# cape.net
KiCad netlist of a schematic drawn in EAGLE
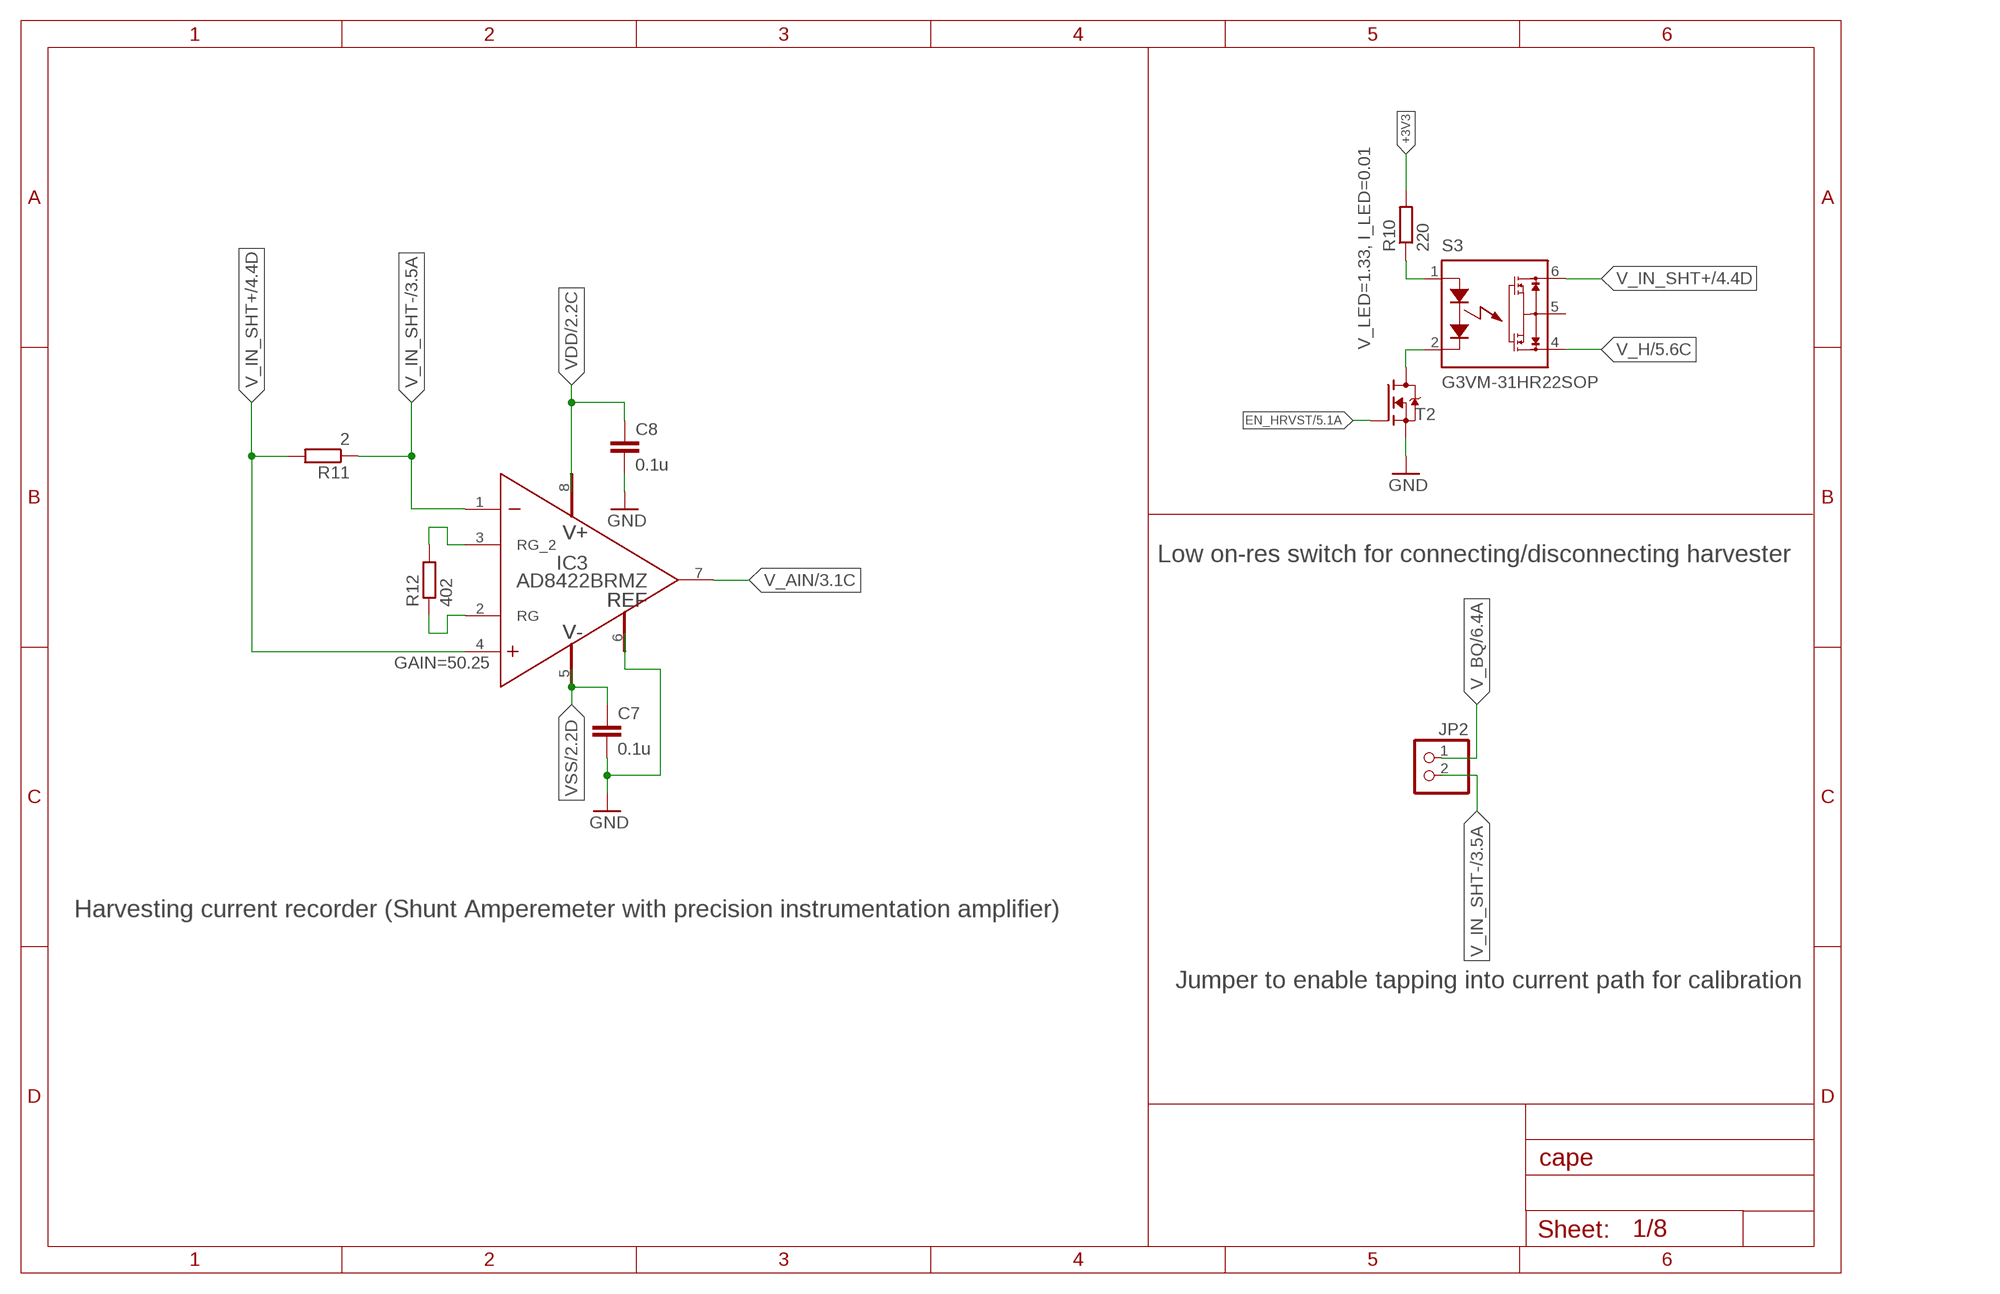
[diagram p0: schematic, sheet 1]
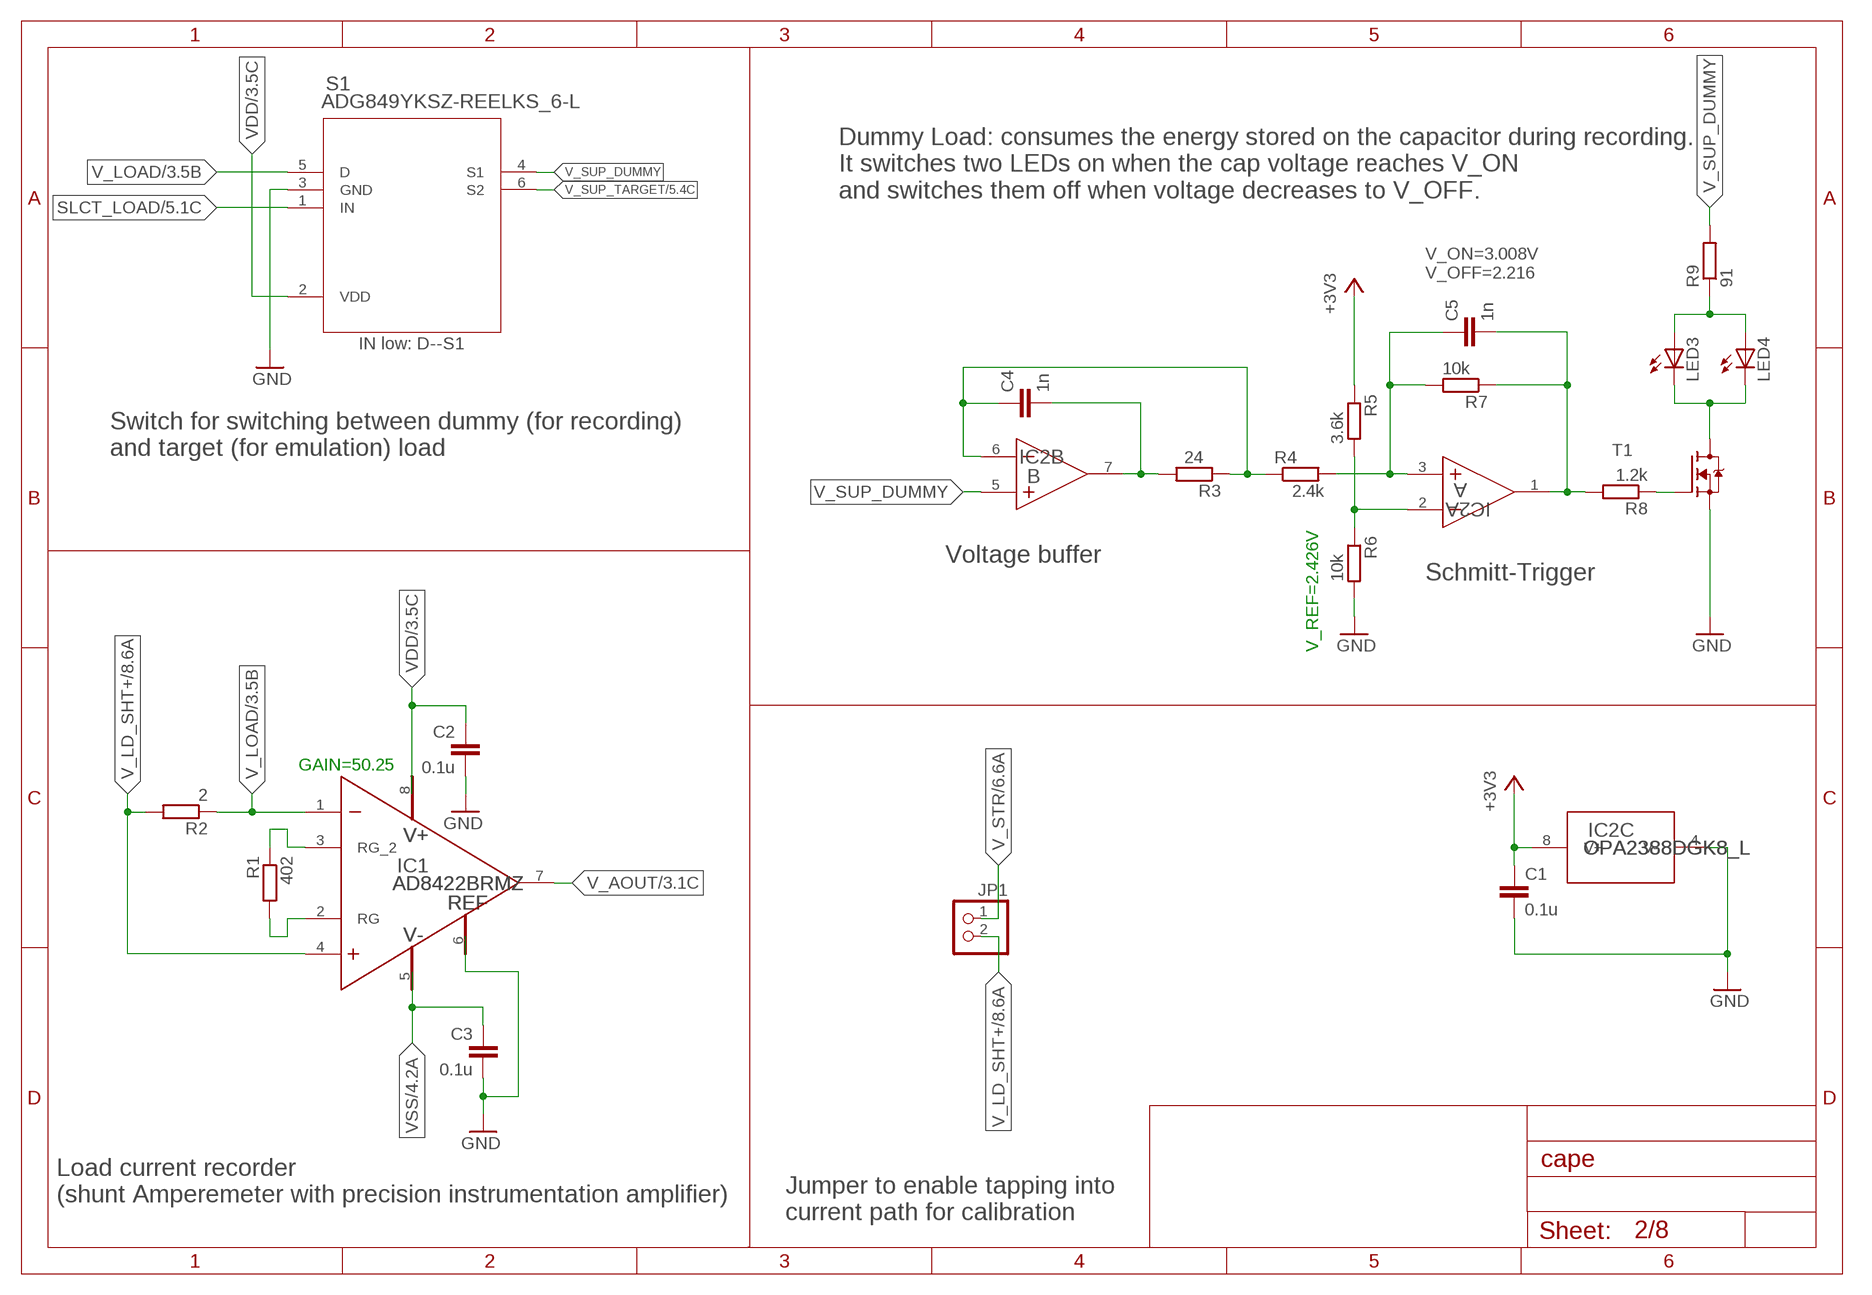
[diagram p1: schematic, sheet 2]
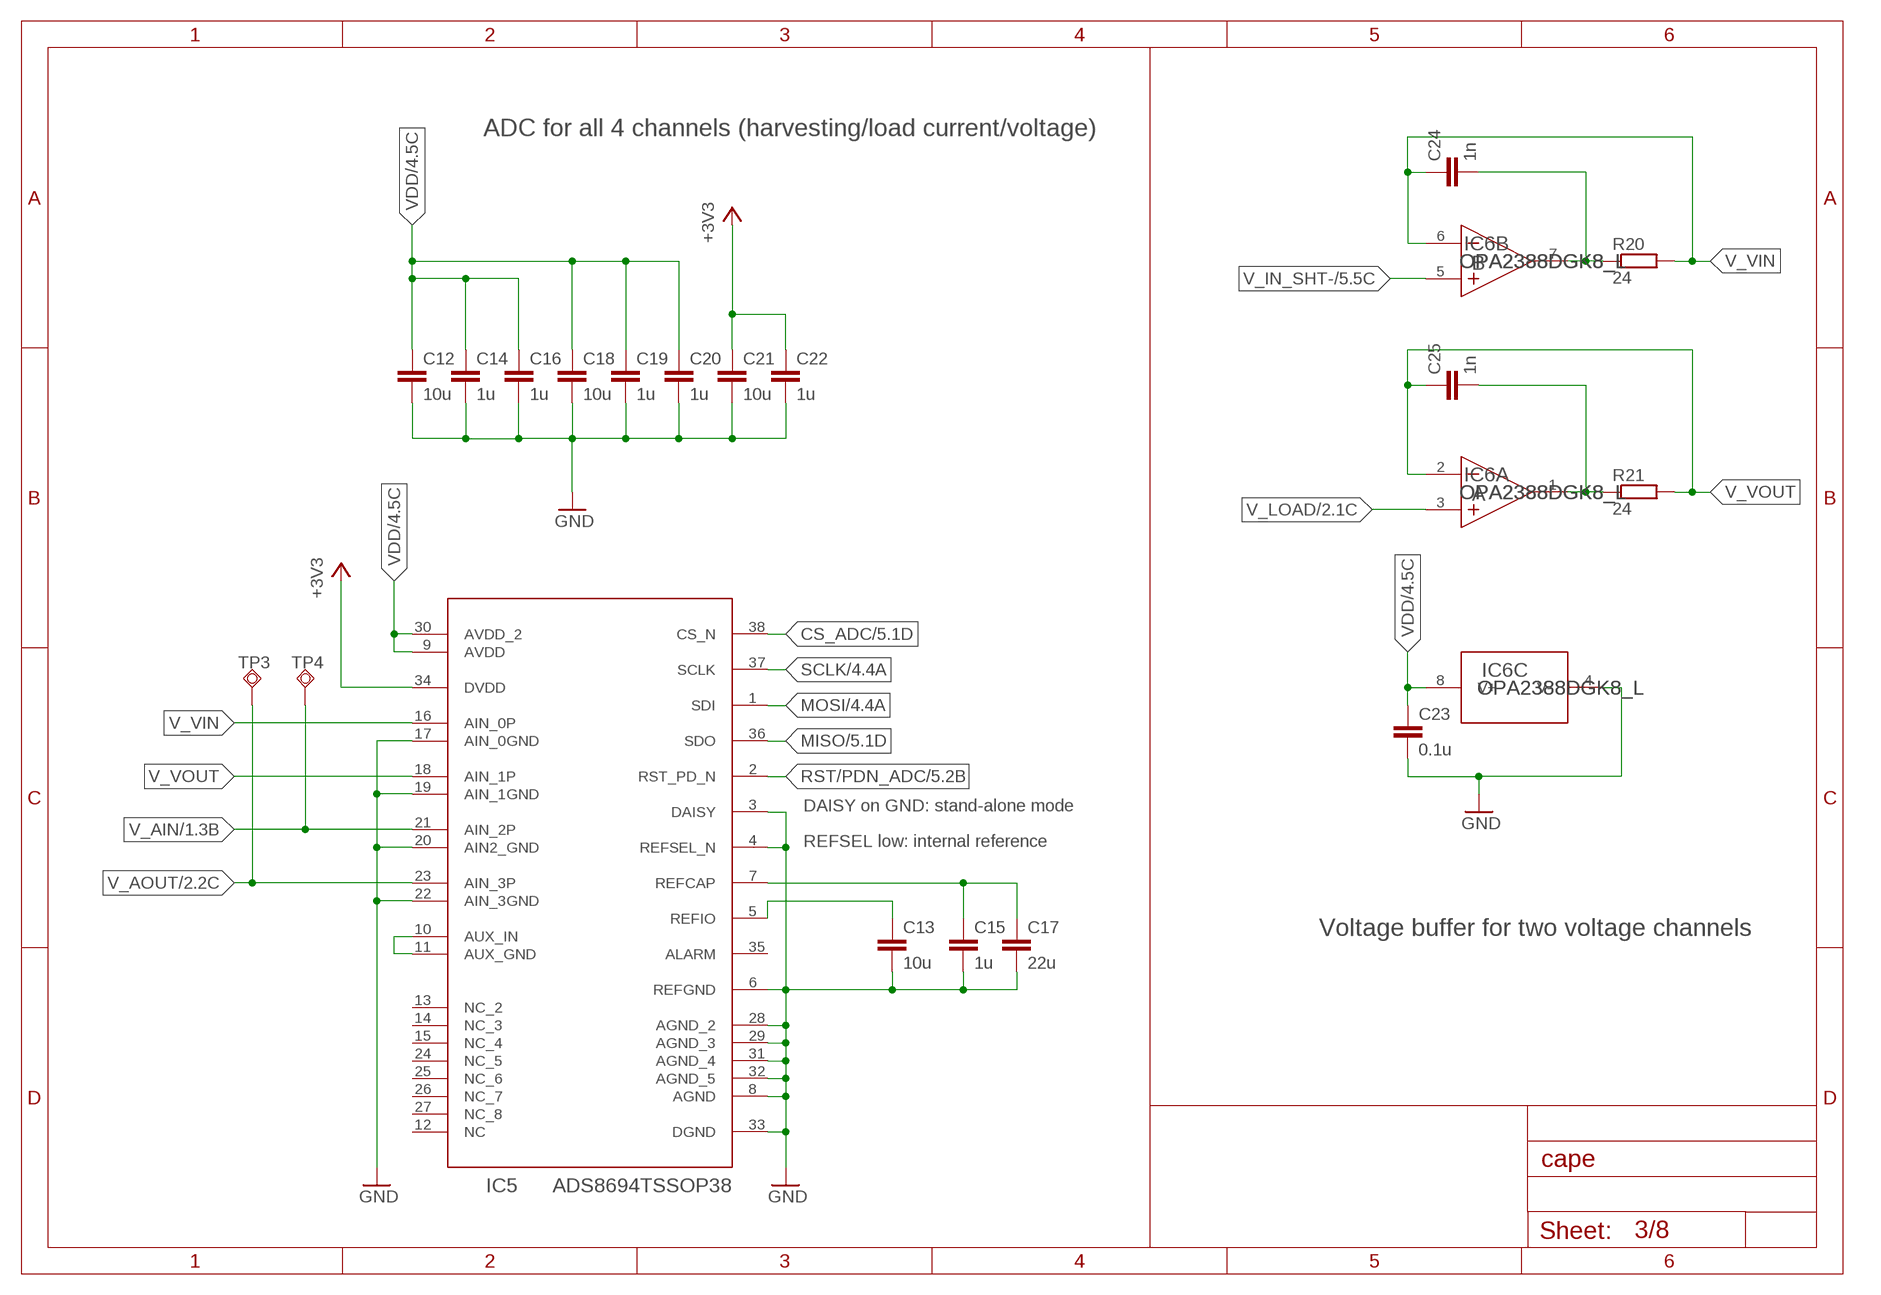
[diagram p2: schematic, sheet 3]
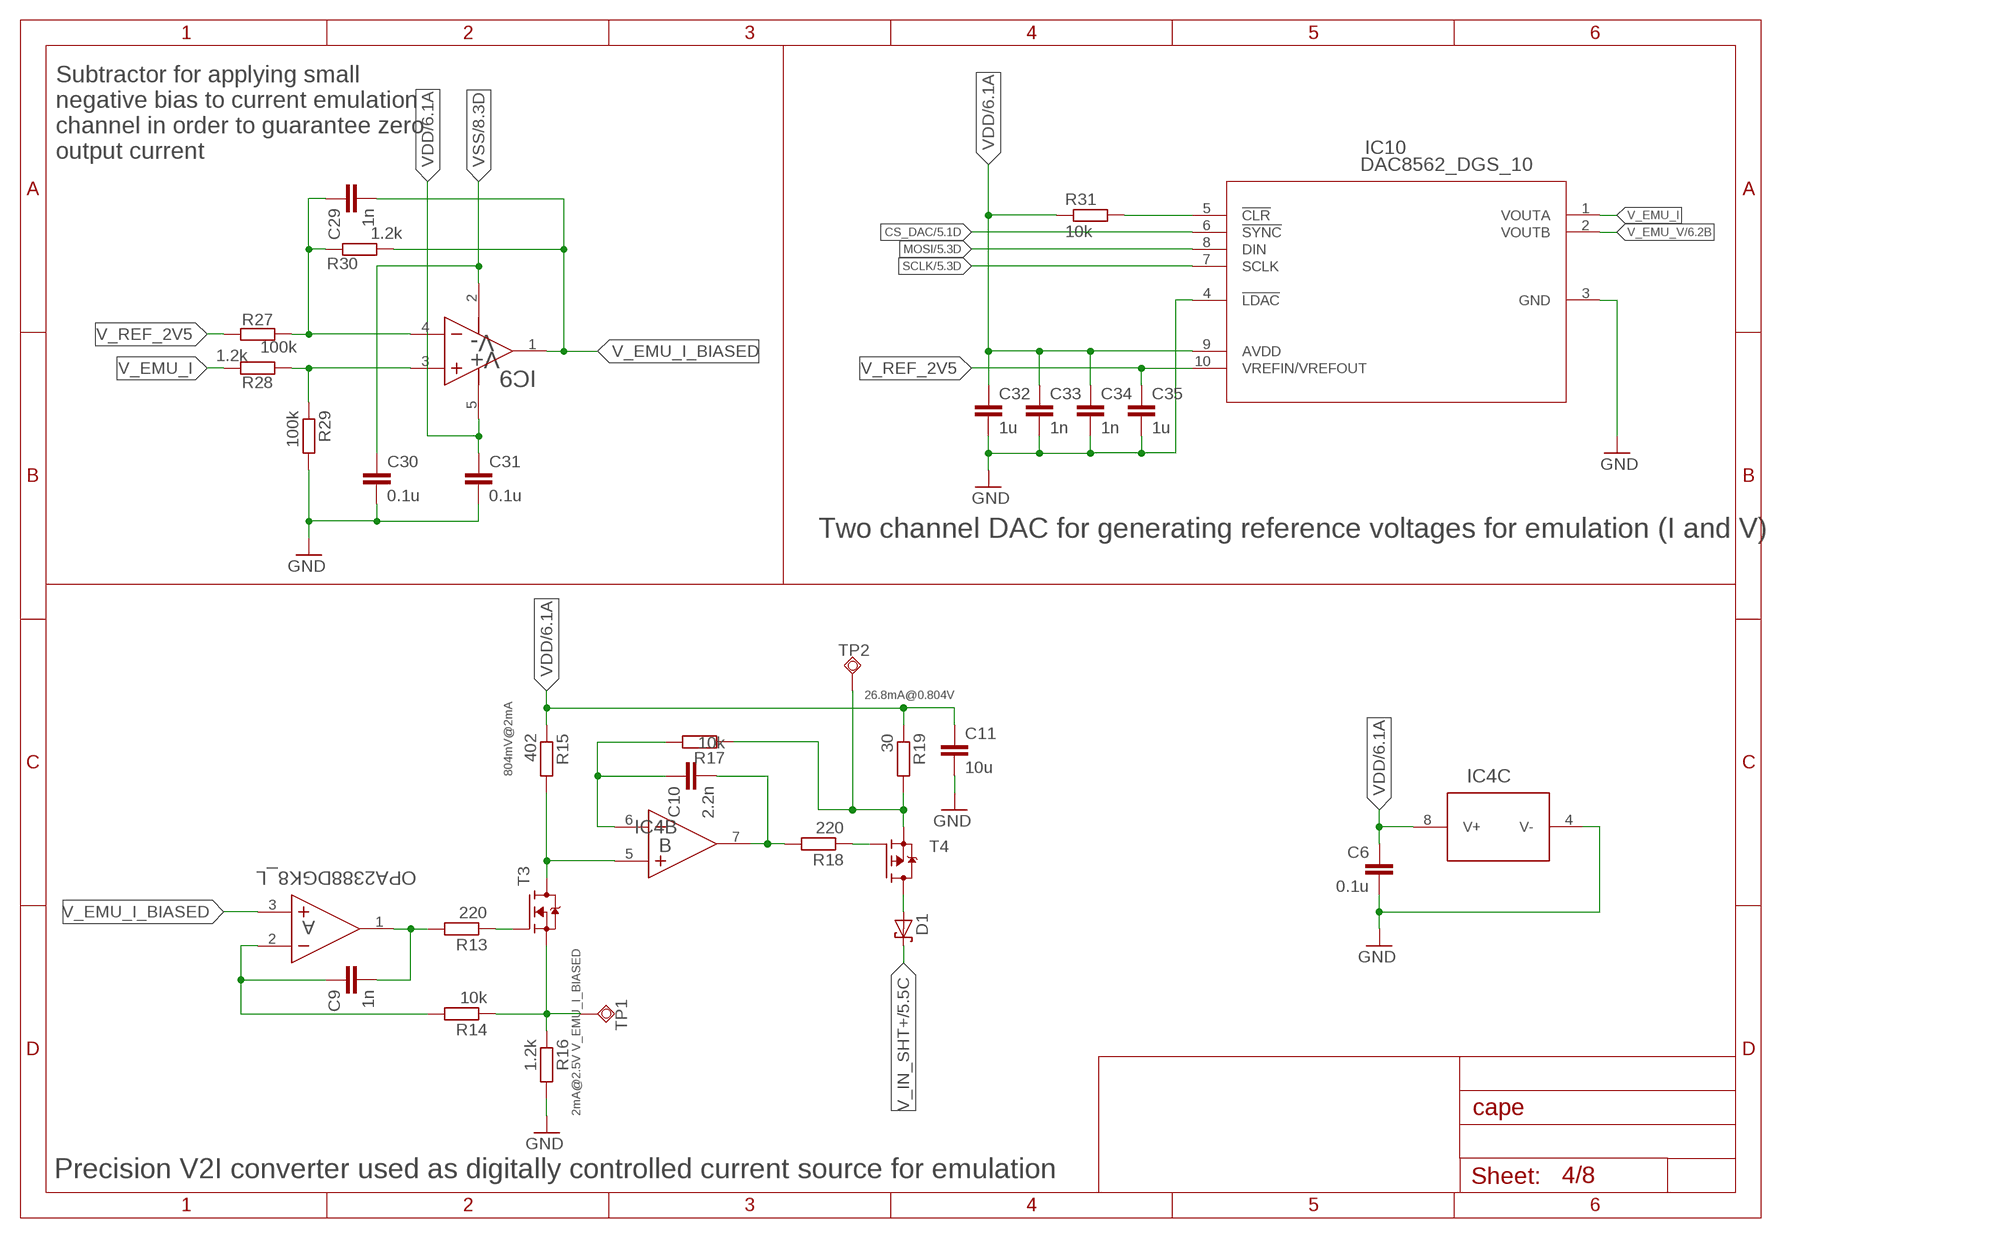
[diagram p3: schematic, sheet 4]
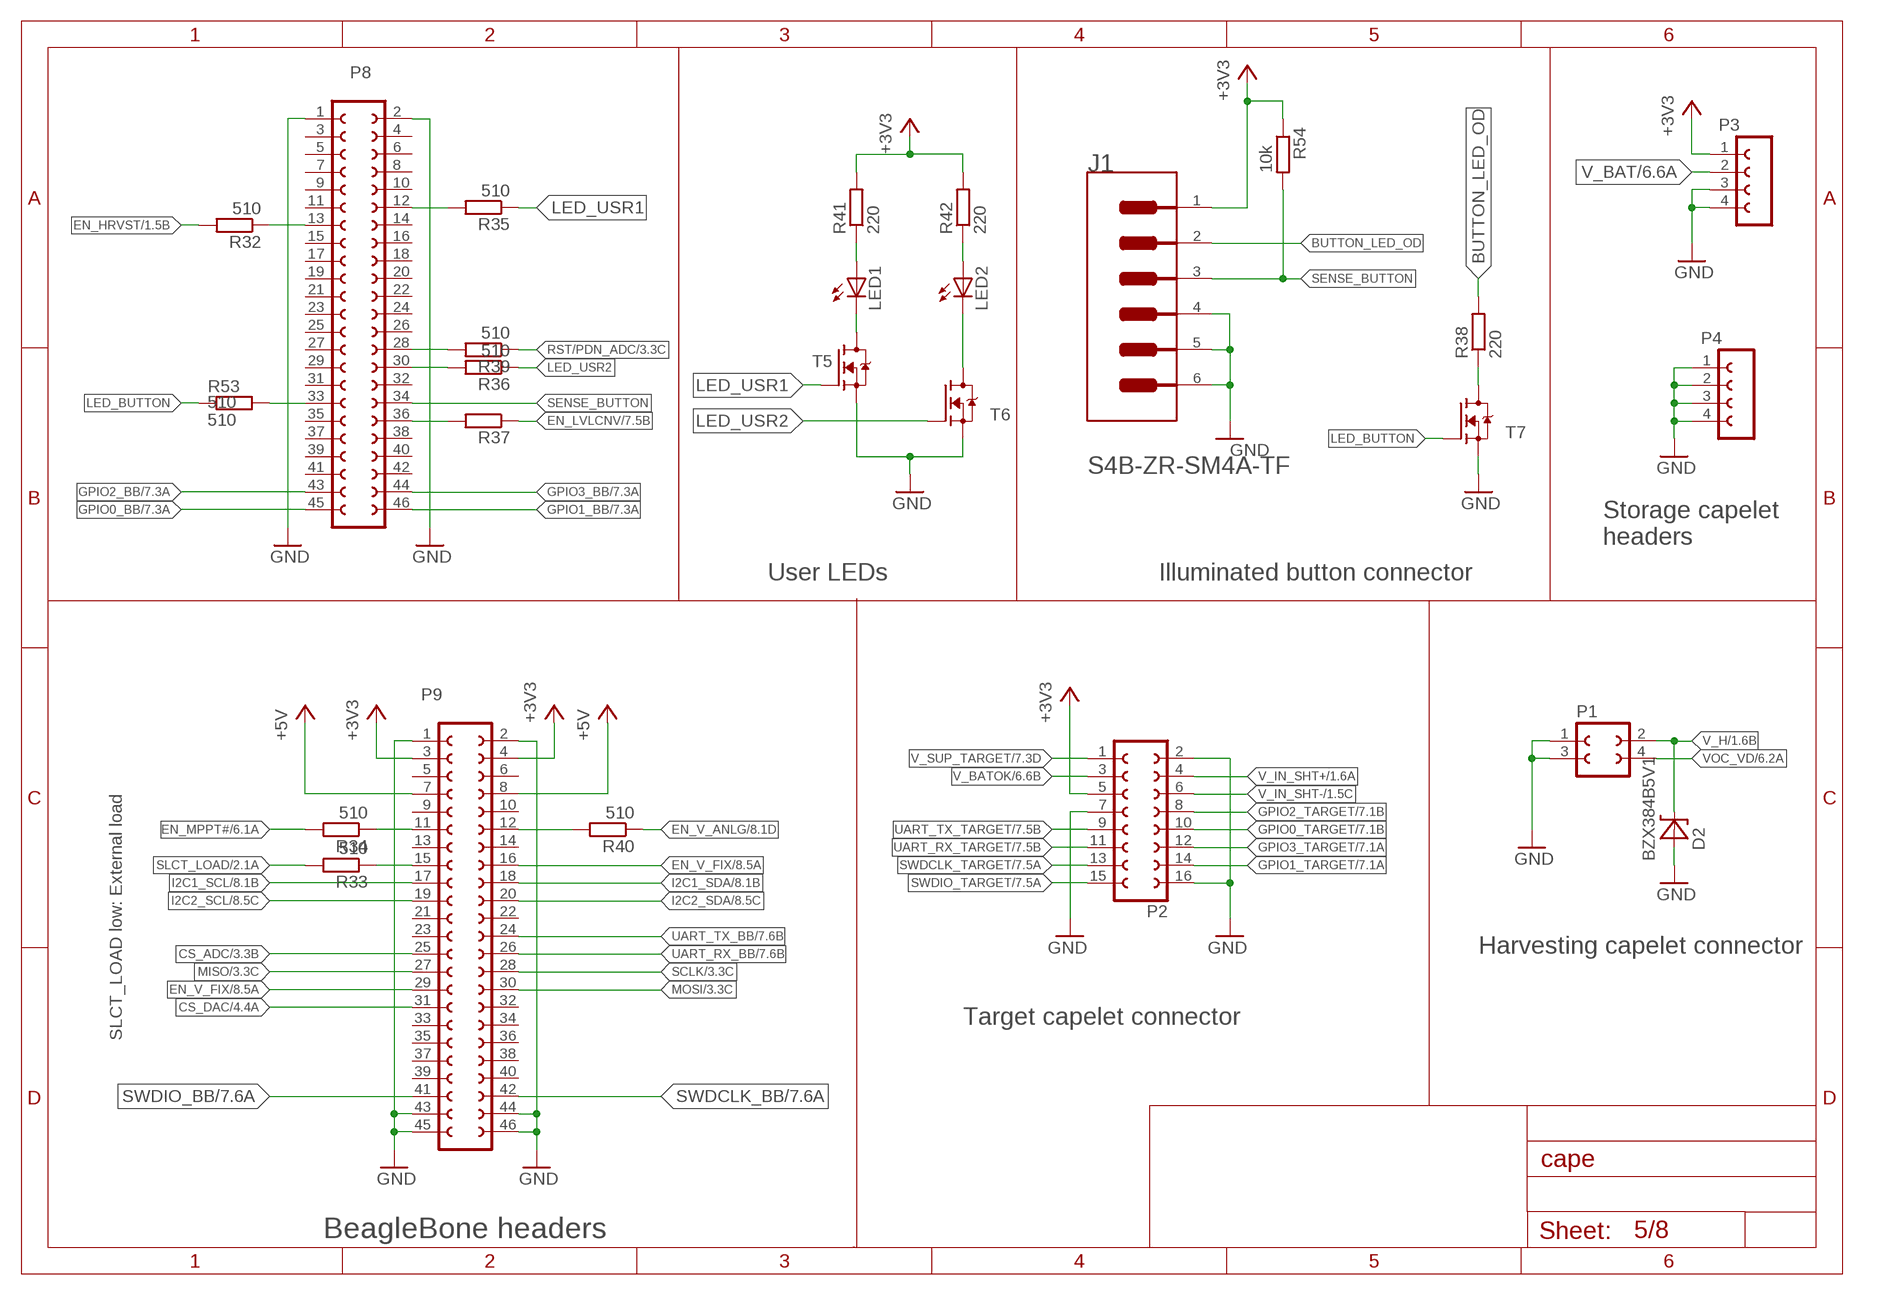
[diagram p4: schematic, sheet 5]
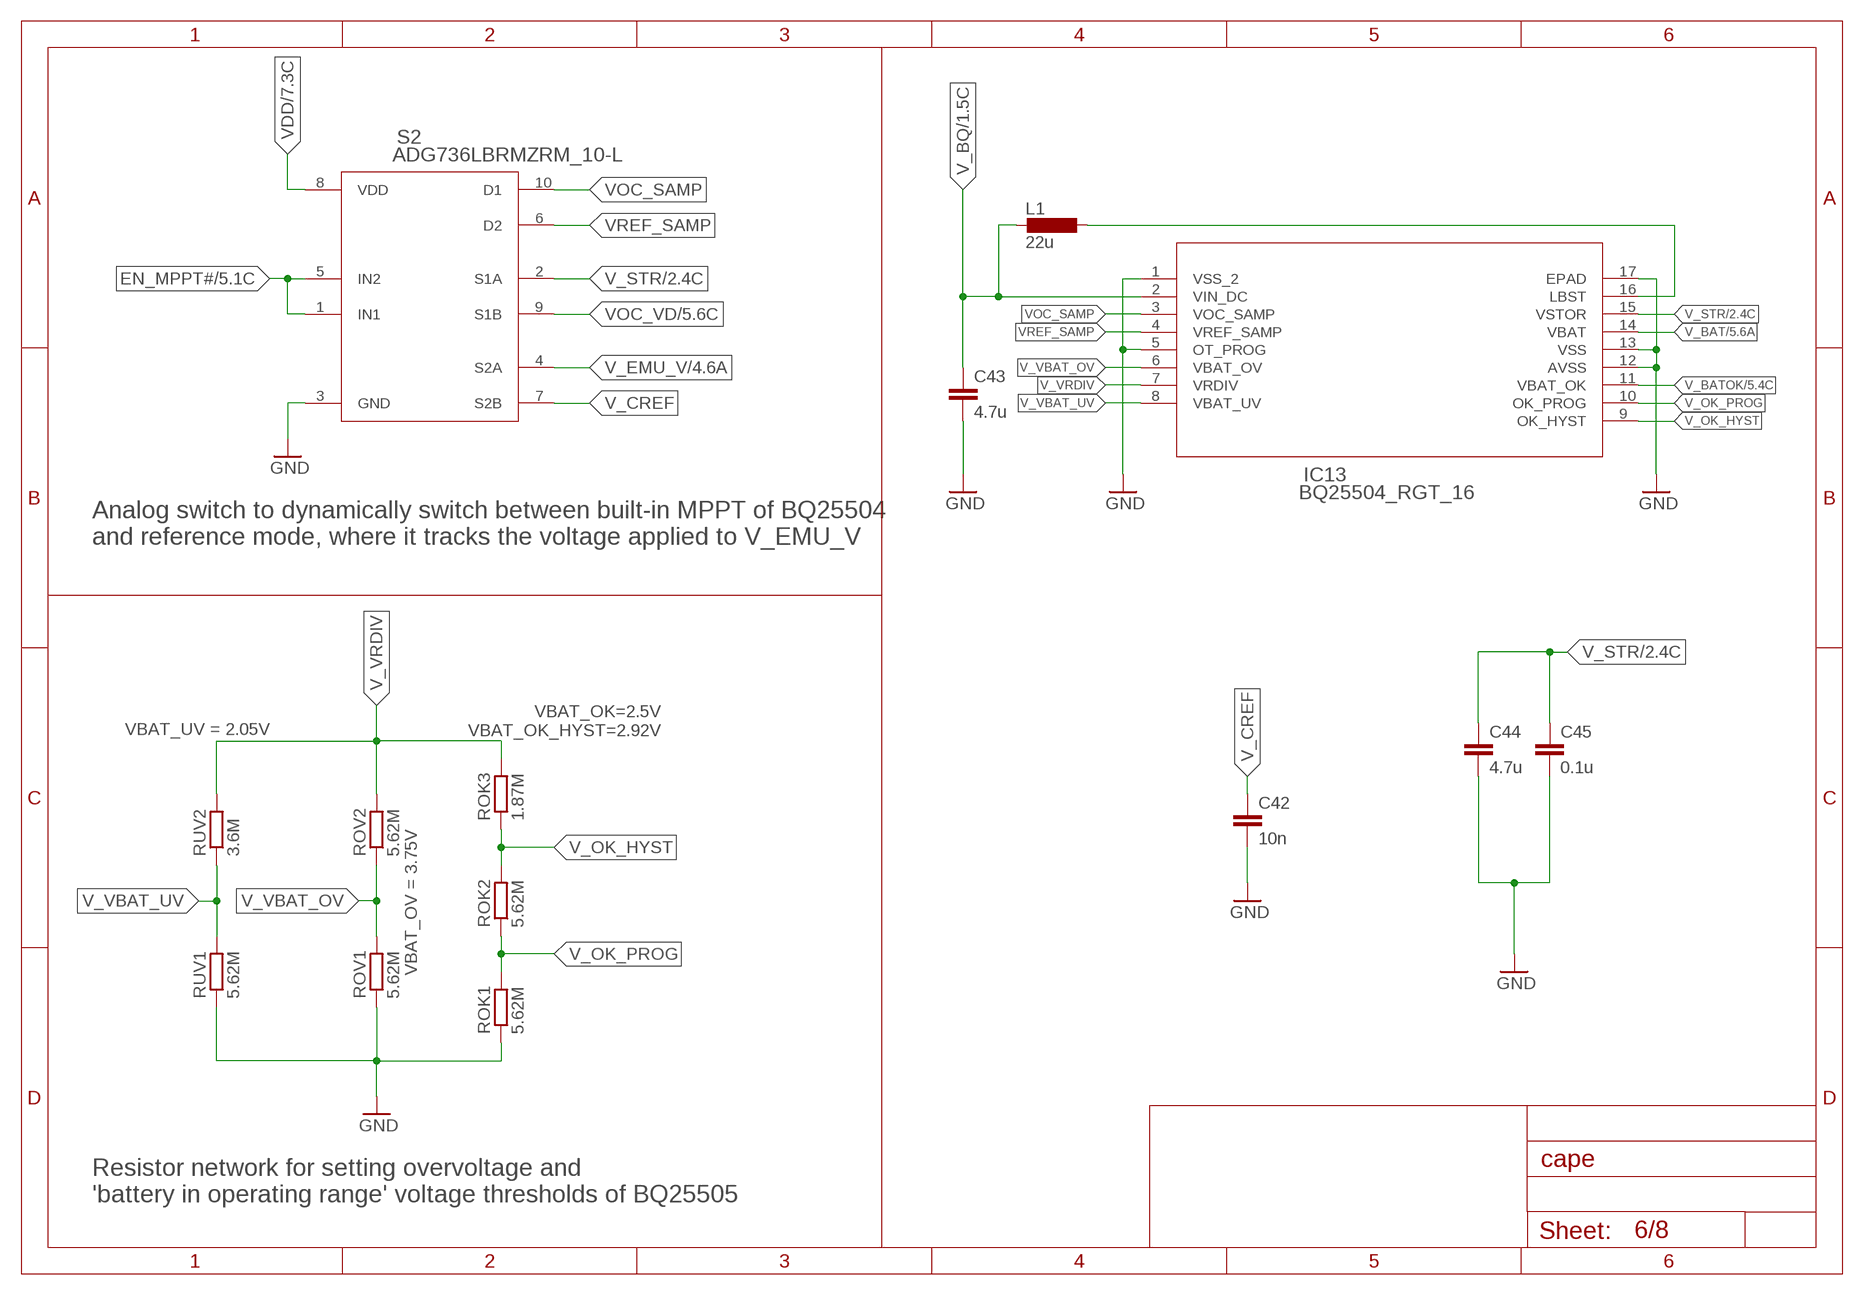
[diagram p5: schematic, sheet 6]
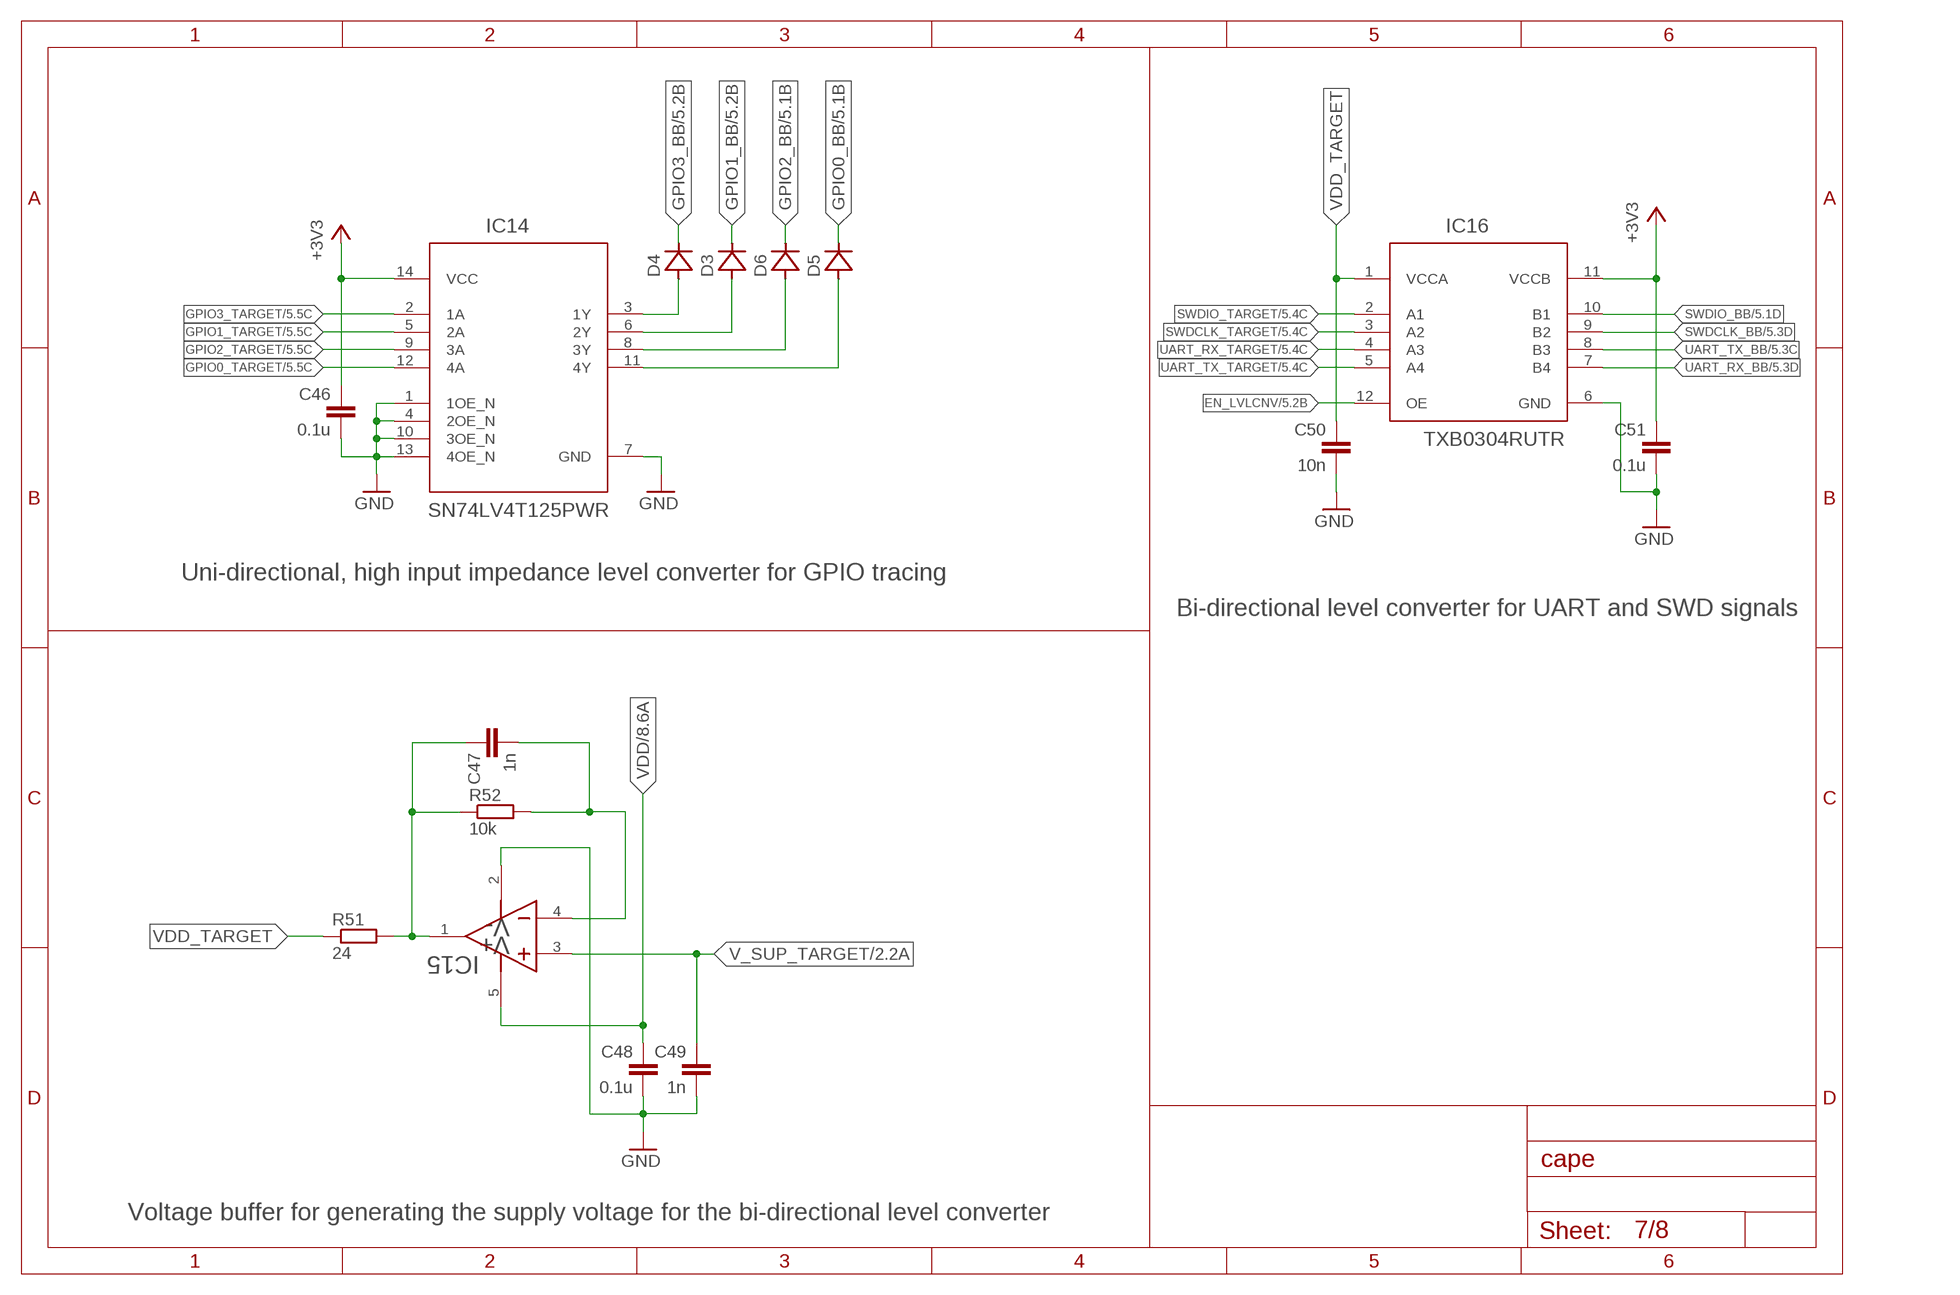
[diagram p6: schematic, sheet 7]
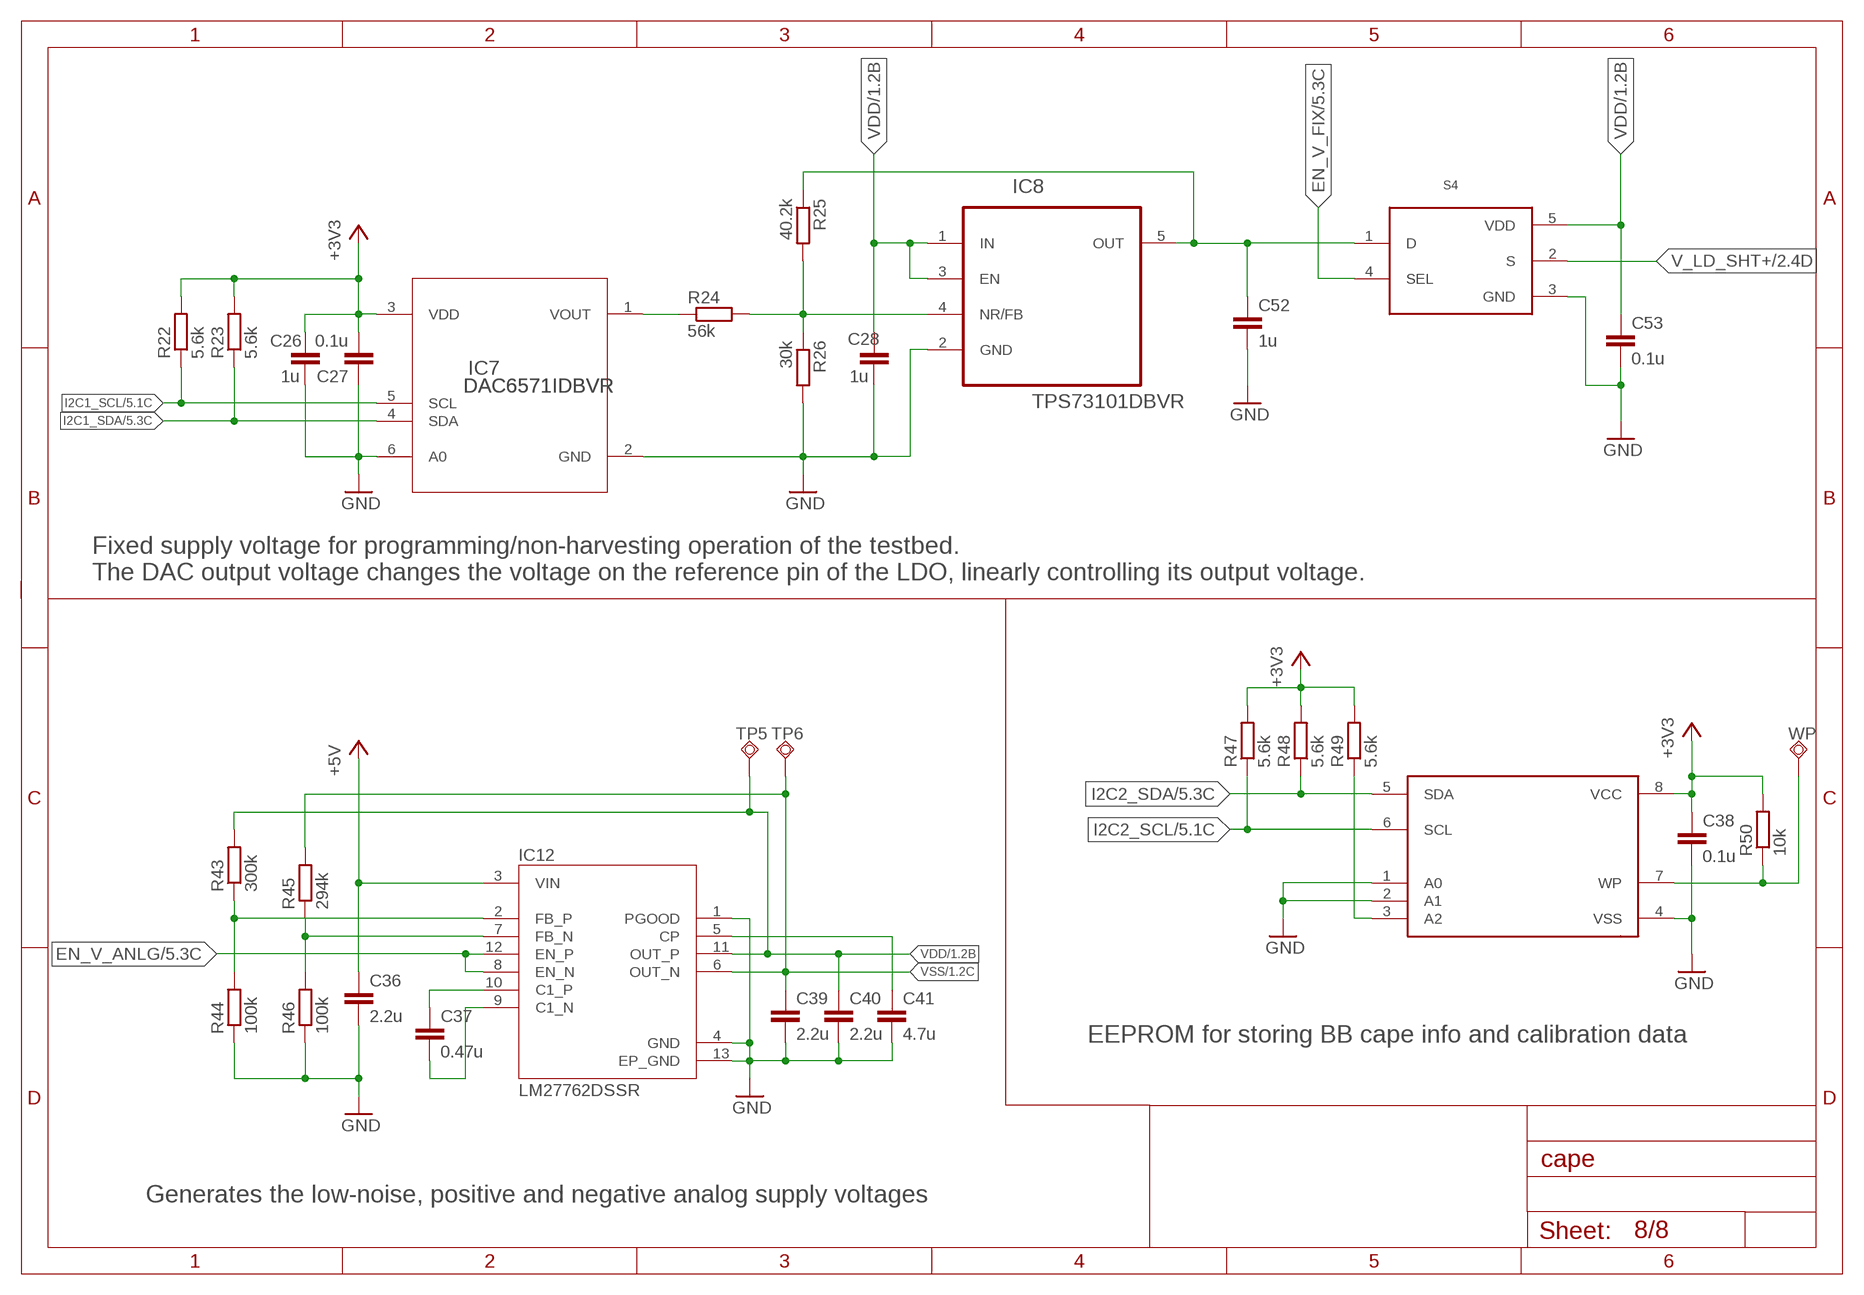
[diagram p7: schematic, sheet 8]

(export (version "E")
  (design (tool "Eeschema 10.0.6"))
  (components
    (comp (ref "C6")
      (value "0.1u")
      (footprint "eagle-import:CAPC1005X55")
      (libsource (lib "eagle-import") (part "C_SMD0402"))
    )
    (comp (ref "C9")
      (value "1n")
      (footprint "eagle-import:CAPC1005X55")
      (libsource (lib "eagle-import") (part "C_SMD0402"))
    )
    (comp (ref "C10")
      (value "2.2n")
      (footprint "eagle-import:CAPC1005X55")
      (libsource (lib "eagle-import") (part "C_SMD0402"))
    )
    (comp (ref "C11")
      (value "10u")
      (footprint "eagle-import:CAPC2012X145")
      (libsource (lib "eagle-import") (part "C_SMD0805"))
    )
    (comp (ref "C29")
      (value "1n")
      (footprint "eagle-import:CAPC1005X55")
      (libsource (lib "eagle-import") (part "C_SMD0402"))
    )
    (comp (ref "C30")
      (value "0.1u")
      (footprint "eagle-import:CAPC1005X55")
      (libsource (lib "eagle-import") (part "C_SMD0402"))
    )
    (comp (ref "C31")
      (value "0.1u")
      (footprint "eagle-import:CAPC1005X55")
      (libsource (lib "eagle-import") (part "C_SMD0402"))
    )
    (comp (ref "C32")
      (value "1u")
      (footprint "eagle-import:CAPC1608X95")
      (libsource (lib "eagle-import") (part "C_SMD0603"))
    )
    (comp (ref "C33")
      (value "1n")
      (footprint "eagle-import:CAPC1005X55")
      (libsource (lib "eagle-import") (part "C_SMD0402"))
    )
    (comp (ref "C34")
      (value "1n")
      (footprint "eagle-import:CAPC1005X55")
      (libsource (lib "eagle-import") (part "C_SMD0402"))
    )
    (comp (ref "C35")
      (value "1u")
      (footprint "eagle-import:CAPC1608X95")
      (libsource (lib "eagle-import") (part "C_SMD0603"))
    )
    (comp (ref "D1")
      (value "BAT43WS-HE3SOD-323")
      (footprint "eagle-import:SOD2513X110")
      (libsource (lib "eagle-import") (part "BAT43WS-HE3SOD-323"))
    )
    (comp (ref "IC4")
      (value "OPA2388DGK8_L")
      (footprint "eagle-import:DGK8-L")
      (libsource (lib "eagle-import") (part "OPA2388DGK8_L"))
    )
    (comp (ref "IC9")
      (value "LMP7701MF")
      (footprint "eagle-import:DBV5-L")
      (libsource (lib "eagle-import") (part "LMP7701MF"))
    )
    (comp (ref "IC10")
      (value "DAC8562_DGS_10")
      (footprint "eagle-import:DGS10")
      (libsource (lib "eagle-import") (part "DAC8562_DGS_10"))
    )
    (comp (ref "R13")
      (value "220")
      (footprint "eagle-import:RESC1608X55")
      (libsource (lib "eagle-import") (part "R_SMD0603"))
    )
    (comp (ref "R14")
      (value "10k")
      (footprint "eagle-import:RESC1005X40")
      (libsource (lib "eagle-import") (part "R_SMD0402"))
    )
    (comp (ref "R15")
      (value "402")
      (footprint "eagle-import:RESC1608X55")
      (libsource (lib "eagle-import") (part "R_SMD0603"))
    )
    (comp (ref "R16")
      (value "1.2k")
      (footprint "eagle-import:RESC1005X40")
      (libsource (lib "eagle-import") (part "R_SMD0402"))
    )
    (comp (ref "R17")
      (value "10k")
      (footprint "eagle-import:RESC1005X40")
      (libsource (lib "eagle-import") (part "R_SMD0402"))
    )
    (comp (ref "R18")
      (value "220")
      (footprint "eagle-import:RESC1608X55")
      (libsource (lib "eagle-import") (part "R_SMD0603"))
    )
    (comp (ref "R19")
      (value "30")
      (footprint "eagle-import:RESC1005X40")
      (libsource (lib "eagle-import") (part "R_SMD0402"))
    )
    (comp (ref "R27")
      (value "100k")
      (footprint "eagle-import:RESC1005X40")
      (libsource (lib "eagle-import") (part "R_SMD0402"))
    )
    (comp (ref "R28")
      (value "1.2k")
      (footprint "eagle-import:RESC1005X40")
      (libsource (lib "eagle-import") (part "R_SMD0402"))
    )
    (comp (ref "R29")
      (value "100k")
      (footprint "eagle-import:RESC1005X40")
      (libsource (lib "eagle-import") (part "R_SMD0402"))
    )
    (comp (ref "R30")
      (value "1.2k")
      (footprint "eagle-import:RESC1005X40")
      (libsource (lib "eagle-import") (part "R_SMD0402"))
    )
    (comp (ref "R31")
      (value "10k")
      (footprint "eagle-import:RESC1005X40")
      (libsource (lib "eagle-import") (part "R_SMD0402"))
    )
    (comp (ref "T3")
      (value "SI2374DSSOT23-VSHAY")
      (footprint "eagle-import:SOT95P237X112-3")
      (libsource (lib "eagle-import") (part "SI2374DSSOT23-VSHAY"))
    )
    (comp (ref "T4")
      (value "SI2307SOT23-VSHAY")
      (footprint "eagle-import:SOT95P237X112-3")
      (libsource (lib "eagle-import") (part "SI2307SOT23-VSHAY"))
    )
    (comp (ref "TP1")
      (value "TPSQTP06R")
      (footprint "eagle-import:TP06R")
      (libsource (lib "eagle-import") (part "TPSQTP06R"))
    )
    (comp (ref "TP2")
      (value "TPSQTP06R")
      (footprint "eagle-import:TP06R")
      (libsource (lib "eagle-import") (part "TPSQTP06R"))
    )
    (comp (ref "C12")
      (value "10u")
      (footprint "eagle-import:CAPC2012X145")
      (libsource (lib "eagle-import") (part "C_SMD0805"))
    )
    (comp (ref "C13")
      (value "10u")
      (footprint "eagle-import:CAPC2012X145")
      (libsource (lib "eagle-import") (part "C_SMD0805"))
    )
    (comp (ref "C14")
      (value "1u")
      (footprint "eagle-import:CAPC1608X95")
      (libsource (lib "eagle-import") (part "C_SMD0603"))
    )
    (comp (ref "C15")
      (value "1u")
      (footprint "eagle-import:CAPC1608X95")
      (libsource (lib "eagle-import") (part "C_SMD0603"))
    )
    (comp (ref "C16")
      (value "1u")
      (footprint "eagle-import:CAPC1608X95")
      (libsource (lib "eagle-import") (part "C_SMD0603"))
    )
    (comp (ref "C17")
      (value "22u")
      (footprint "eagle-import:CAPC3225X280")
      (libsource (lib "eagle-import") (part "C_SMD1210"))
    )
    (comp (ref "C18")
      (value "10u")
      (footprint "eagle-import:CAPC2012X145")
      (libsource (lib "eagle-import") (part "C_SMD0805"))
    )
    (comp (ref "C19")
      (value "1u")
      (footprint "eagle-import:CAPC1608X95")
      (libsource (lib "eagle-import") (part "C_SMD0603"))
    )
    (comp (ref "C20")
      (value "1u")
      (footprint "eagle-import:CAPC1608X95")
      (libsource (lib "eagle-import") (part "C_SMD0603"))
    )
    (comp (ref "C21")
      (value "10u")
      (footprint "eagle-import:CAPC2012X145")
      (libsource (lib "eagle-import") (part "C_SMD0805"))
    )
    (comp (ref "C22")
      (value "1u")
      (footprint "eagle-import:CAPC1608X95")
      (libsource (lib "eagle-import") (part "C_SMD0603"))
    )
    (comp (ref "C23")
      (value "0.1u")
      (footprint "eagle-import:CAPC1005X55")
      (libsource (lib "eagle-import") (part "C_SMD0402"))
    )
    (comp (ref "C24")
      (value "1n")
      (footprint "eagle-import:CAPC1005X55")
      (libsource (lib "eagle-import") (part "C_SMD0402"))
    )
    (comp (ref "C25")
      (value "1n")
      (footprint "eagle-import:CAPC1005X55")
      (libsource (lib "eagle-import") (part "C_SMD0402"))
    )
    (comp (ref "IC5")
      (value "ADS8694TSSOP38")
      (footprint "eagle-import:TSSOP38")
      (libsource (lib "eagle-import") (part "ADS8694TSSOP38"))
    )
    (comp (ref "IC6")
      (value "OPA2388DGK8_L")
      (footprint "eagle-import:DGK8-L")
      (libsource (lib "eagle-import") (part "OPA2388DGK8_L"))
    )
    (comp (ref "R20")
      (value "24")
      (footprint "eagle-import:RESC1005X40")
      (libsource (lib "eagle-import") (part "R_SMD0402"))
    )
    (comp (ref "R21")
      (value "24")
      (footprint "eagle-import:RESC1005X40")
      (libsource (lib "eagle-import") (part "R_SMD0402"))
    )
    (comp (ref "TP3")
      (value "TPSQTP06R")
      (footprint "eagle-import:TP06R")
      (libsource (lib "eagle-import") (part "TPSQTP06R"))
    )
    (comp (ref "TP4")
      (value "TPSQTP06R")
      (footprint "eagle-import:TP06R")
      (libsource (lib "eagle-import") (part "TPSQTP06R"))
    )
    (comp (ref "C26")
      (value "1u")
      (footprint "eagle-import:CAPC1608X95")
      (libsource (lib "eagle-import") (part "C_SMD0603"))
    )
    (comp (ref "C27")
      (value "0.1u")
      (footprint "eagle-import:CAPC1005X55")
      (libsource (lib "eagle-import") (part "C_SMD0402"))
    )
    (comp (ref "C28")
      (value "1u")
      (footprint "eagle-import:CAPC1608X95")
      (libsource (lib "eagle-import") (part "C_SMD0603"))
    )
    (comp (ref "C36")
      (value "2.2u")
      (footprint "eagle-import:CAPC2012X145")
      (libsource (lib "eagle-import") (part "C_SMD0805"))
    )
    (comp (ref "C37")
      (value "0.47u")
      (footprint "eagle-import:CAPC1608X95")
      (libsource (lib "eagle-import") (part "C_SMD0603"))
    )
    (comp (ref "C38")
      (value "0.1u")
      (footprint "eagle-import:CAPC1005X55")
      (libsource (lib "eagle-import") (part "C_SMD0402"))
    )
    (comp (ref "C39")
      (value "2.2u")
      (footprint "eagle-import:CAPC2012X145")
      (libsource (lib "eagle-import") (part "C_SMD0805"))
    )
    (comp (ref "C40")
      (value "2.2u")
      (footprint "eagle-import:CAPC2012X145")
      (libsource (lib "eagle-import") (part "C_SMD0805"))
    )
    (comp (ref "C41")
      (value "4.7u")
      (footprint "eagle-import:CAPC2012X145")
      (libsource (lib "eagle-import") (part "C_SMD0805"))
    )
    (comp (ref "C52")
      (value "1u")
      (footprint "eagle-import:CAPC1608X95")
      (libsource (lib "eagle-import") (part "shepherd_C_SMD0603"))
    )
    (comp (ref "C53")
      (value "0.1u")
      (footprint "eagle-import:CAPC1005X55")
      (libsource (lib "eagle-import") (part "C_SMD0402"))
    )
    (comp (ref "IC7")
      (value "DAC6571IDBVR")
      (footprint "eagle-import:DAC6571IDBVR")
      (libsource (lib "eagle-import") (part "DAC6571IDBVR"))
    )
    (comp (ref "IC8")
      (value "TPS73101DBVR")
      (footprint "eagle-import:SOT95P280X145-5N")
      (fields (field (name "MF") "Texas Instruments"))
      (libsource (lib "eagle-import") (part "TPS73101DBVR"))
    )
    (comp (ref "IC11")
      (value "CAT24C256WI-GT3")
      (footprint "eagle-import:SO08")
      (libsource (lib "eagle-import") (part "CAT24C256WI-GT3"))
    )
    (comp (ref "IC12")
      (value "LM27762DSSR")
      (footprint "eagle-import:VREG_LM27762DSSR")
      (fields (field (name "MF") "Texas Instruments"))
      (libsource (lib "eagle-import") (part "LM27762DSSR"))
    )
    (comp (ref "R22")
      (value "5.6k")
      (footprint "eagle-import:RESC1005X40")
      (libsource (lib "eagle-import") (part "R_SMD0402"))
    )
    (comp (ref "R23")
      (value "5.6k")
      (footprint "eagle-import:RESC1005X40")
      (libsource (lib "eagle-import") (part "R_SMD0402"))
    )
    (comp (ref "R24")
      (value "56k")
      (footprint "eagle-import:RESC1005X40")
      (libsource (lib "eagle-import") (part "R_SMD0402"))
    )
    (comp (ref "R25")
      (value "40.2k")
      (footprint "eagle-import:RESC1005X40")
      (libsource (lib "eagle-import") (part "R_SMD0402"))
    )
    (comp (ref "R26")
      (value "30k")
      (footprint "eagle-import:RESC1005X40")
      (libsource (lib "eagle-import") (part "R_SMD0402"))
    )
    (comp (ref "R43")
      (value "300k")
      (footprint "eagle-import:RESC1005X40")
      (libsource (lib "eagle-import") (part "R_SMD0402"))
    )
    (comp (ref "R44")
      (value "100k")
      (footprint "eagle-import:RESC1005X40")
      (libsource (lib "eagle-import") (part "R_SMD0402"))
    )
    (comp (ref "R45")
      (value "294k")
      (footprint "eagle-import:RESC1005X40")
      (libsource (lib "eagle-import") (part "R_SMD0402"))
    )
    (comp (ref "R46")
      (value "100k")
      (footprint "eagle-import:RESC1005X40")
      (libsource (lib "eagle-import") (part "R_SMD0402"))
    )
    (comp (ref "R47")
      (value "5.6k")
      (footprint "eagle-import:RESC1005X40")
      (libsource (lib "eagle-import") (part "R_SMD0402"))
    )
    (comp (ref "R48")
      (value "5.6k")
      (footprint "eagle-import:RESC1005X40")
      (libsource (lib "eagle-import") (part "R_SMD0402"))
    )
    (comp (ref "R49")
      (value "5.6k")
      (footprint "eagle-import:RESC1005X40")
      (libsource (lib "eagle-import") (part "R_SMD0402"))
    )
    (comp (ref "R50")
      (value "10k")
      (footprint "eagle-import:RESC1005X40")
      (libsource (lib "eagle-import") (part "R_SMD0402"))
    )
    (comp (ref "S4")
      (value "TMUX1101DCK")
      (footprint "eagle-import:DCK5")
      (libsource (lib "eagle-import") (part "TMUX1101DCK"))
    )
    (comp (ref "TP5")
      (value "TPSQTP06R")
      (footprint "eagle-import:TP06R")
      (libsource (lib "eagle-import") (part "TPSQTP06R"))
    )
    (comp (ref "TP6")
      (value "TPSQTP06R")
      (footprint "eagle-import:TP06R")
      (libsource (lib "eagle-import") (part "TPSQTP06R"))
    )
    (comp (ref "WP")
      (value "TPSQTP06R")
      (footprint "eagle-import:TP06R")
      (libsource (lib "eagle-import") (part "TPSQTP06R"))
    )
    (comp (ref "C46")
      (value "0.1u")
      (footprint "eagle-import:CAPC1005X55")
      (libsource (lib "eagle-import") (part "C_SMD0402"))
    )
    (comp (ref "C47")
      (value "1n")
      (footprint "eagle-import:CAPC1005X55")
      (libsource (lib "eagle-import") (part "C_SMD0402"))
    )
    (comp (ref "C48")
      (value "0.1u")
      (footprint "eagle-import:CAPC1005X55")
      (libsource (lib "eagle-import") (part "C_SMD0402"))
    )
    (comp (ref "C49")
      (value "1n")
      (footprint "eagle-import:CAPC1005X55")
      (libsource (lib "eagle-import") (part "C_SMD0402"))
    )
    (comp (ref "C50")
      (value "10n")
      (footprint "eagle-import:CAPC1005X55")
      (libsource (lib "eagle-import") (part "C_SMD0402"))
    )
    (comp (ref "C51")
      (value "0.1u")
      (footprint "eagle-import:CAPC1005X55")
      (libsource (lib "eagle-import") (part "C_SMD0402"))
    )
    (comp (ref "D3")
      (value "ACDBQC0130L-HF0402")
      (footprint "eagle-import:DIOC1005X55N")
      (libsource (lib "eagle-import") (part "ACDBQC0130L-HF0402"))
    )
    (comp (ref "D4")
      (value "ACDBQC0130L-HF0402")
      (footprint "eagle-import:DIOC1005X55N")
      (libsource (lib "eagle-import") (part "ACDBQC0130L-HF0402"))
    )
    (comp (ref "D5")
      (value "ACDBQC0130L-HF0402")
      (footprint "eagle-import:DIOC1005X55N")
      (libsource (lib "eagle-import") (part "ACDBQC0130L-HF0402"))
    )
    (comp (ref "D6")
      (value "ACDBQC0130L-HF0402")
      (footprint "eagle-import:DIOC1005X55N")
      (libsource (lib "eagle-import") (part "ACDBQC0130L-HF0402"))
    )
    (comp (ref "IC14")
      (value "SN74LV4T125PWR")
      (footprint "eagle-import:PW0014A_N")
      (libsource (lib "eagle-import") (part "SN74LV4T125PWR"))
    )
    (comp (ref "IC15")
      (value "LMP7701MF")
      (footprint "eagle-import:DBV5-L")
      (libsource (lib "eagle-import") (part "LMP7701MF"))
    )
    (comp (ref "IC16")
      (value "TXB0304RUTR")
      (footprint "eagle-import:RUT0012A")
      (libsource (lib "eagle-import") (part "TXB0304RUTR"))
    )
    (comp (ref "R51")
      (value "24")
      (footprint "eagle-import:RESC1005X40")
      (libsource (lib "eagle-import") (part "R_SMD0402"))
    )
    (comp (ref "R52")
      (value "10k")
      (footprint "eagle-import:RESC1005X40")
      (libsource (lib "eagle-import") (part "R_SMD0402"))
    )
    (comp (ref "C7")
      (value "0.1u")
      (footprint "eagle-import:CAPC1005X55")
      (libsource (lib "eagle-import") (part "C_SMD0402"))
    )
    (comp (ref "C8")
      (value "0.1u")
      (footprint "eagle-import:CAPC1005X55")
      (libsource (lib "eagle-import") (part "C_SMD0402"))
    )
    (comp (ref "IC3")
      (value "AD8422BRMZ")
      (footprint "eagle-import:RM_8-L")
      (libsource (lib "eagle-import") (part "AD8422BRMZ"))
    )
    (comp (ref "JP2")
      (value "PINHD-1X2")
      (footprint "eagle-import:1X02")
      (libsource (lib "eagle-import") (part "PINHD-1X2"))
    )
    (comp (ref "R10")
      (value "220")
      (footprint "eagle-import:RESC1608X55")
      (libsource (lib "eagle-import") (part "R_SMD0603"))
    )
    (comp (ref "R11")
      (value "2")
      (footprint "eagle-import:RESC1608X55")
      (libsource (lib "eagle-import") (part "R_SMD0603"))
    )
    (comp (ref "R12")
      (value "402")
      (footprint "eagle-import:RESC1608X55")
      (libsource (lib "eagle-import") (part "R_SMD0603"))
    )
    (comp (ref "S3")
      (value "G3VM-31HR22SOP")
      (footprint "eagle-import:SOP06")
      (libsource (lib "eagle-import") (part "G3VM-31HRSOP22"))
    )
    (comp (ref "T2")
      (value "SI2374DSSOT23-VSHAY")
      (footprint "eagle-import:SOT95P237X112-3")
      (libsource (lib "eagle-import") (part "SI2374DSSOT23-VSHAY"))
    )
    (comp (ref "D2")
      (value "BZX384B5V1")
      (footprint "eagle-import:SOD2513X110")
      (libsource (lib "eagle-import") (part "BZX384B5V1"))
    )
    (comp (ref "J1")
      (value "JST_S4B-ZR-SM4A-TFJST_S4B-ZR-SM4A-TF_0_0")
      (footprint "eagle-import:JST_S4B-ZR-SM4A-TF_0")
      (fields
        (field (name "DIGIKEY_PART_NUMBER") "455-1695-1-ND")
        (field (name "MF") "JST")
        (field (name "MOUSER_PART_NUMBER") "538-502585-0470")
      )
      (libsource (lib "eagle-import") (part "JST_S4B-ZR-SM4A-TFJST_S4B-ZR-SM4A-TF_0_0"))
    )
    (comp (ref "LED1")
      (value "598-8130-107FLED_0805")
      (footprint "eagle-import:LEDC2012X75")
      (libsource (lib "eagle-import") (part "598-8130-107FLED_0805"))
    )
    (comp (ref "LED2")
      (value "598-8130-107FLED_0805")
      (footprint "eagle-import:LEDC2012X75")
      (libsource (lib "eagle-import") (part "598-8130-107FLED_0805"))
    )
    (comp (ref "P1")
      (value "FE02-2")
      (footprint "eagle-import:FE02-2")
      (libsource (lib "eagle-import") (part "FE02-2"))
    )
    (comp (ref "P2")
      (value "FE08-2")
      (footprint "eagle-import:FE08-2")
      (libsource (lib "eagle-import") (part "FE08-2"))
    )
    (comp (ref "P3")
      (value "FE04-1")
      (footprint "eagle-import:FE04-1")
      (libsource (lib "eagle-import") (part "FE04-1"))
    )
    (comp (ref "P4")
      (value "FE04-1")
      (footprint "eagle-import:FE04-1")
      (libsource (lib "eagle-import") (part "FE04-1"))
    )
    (comp (ref "P8")
      (value "FE23-2")
      (footprint "eagle-import:FE23-2")
      (libsource (lib "eagle-import") (part "FE23-2"))
    )
    (comp (ref "P9")
      (value "FE23-2")
      (footprint "eagle-import:FE23-2")
      (libsource (lib "eagle-import") (part "FE23-2"))
    )
    (comp (ref "R32")
      (value "510")
      (footprint "eagle-import:RESC1005X40")
      (libsource (lib "eagle-import") (part "R_SMD0402"))
    )
    (comp (ref "R33")
      (value "510")
      (footprint "eagle-import:RESC1005X40")
      (libsource (lib "eagle-import") (part "R_SMD0402"))
    )
    (comp (ref "R34")
      (value "510")
      (footprint "eagle-import:RESC1005X40")
      (libsource (lib "eagle-import") (part "R_SMD0402"))
    )
    (comp (ref "R35")
      (value "510")
      (footprint "eagle-import:RESC1005X40")
      (libsource (lib "eagle-import") (part "R_SMD0402"))
    )
    (comp (ref "R36")
      (value "510")
      (footprint "eagle-import:RESC1005X40")
      (libsource (lib "eagle-import") (part "R_SMD0402"))
    )
    (comp (ref "R37")
      (value "510")
      (footprint "eagle-import:RESC1005X40")
      (libsource (lib "eagle-import") (part "R_SMD0402"))
    )
    (comp (ref "R38")
      (value "220")
      (footprint "eagle-import:RESC1608X55")
      (libsource (lib "eagle-import") (part "R_SMD0603"))
    )
    (comp (ref "R39")
      (value "510")
      (footprint "eagle-import:RESC1005X40")
      (libsource (lib "eagle-import") (part "R_SMD0402"))
    )
    (comp (ref "R40")
      (value "510")
      (footprint "eagle-import:RESC1005X40")
      (libsource (lib "eagle-import") (part "R_SMD0402"))
    )
    (comp (ref "R41")
      (value "220")
      (footprint "eagle-import:RESC1608X55")
      (libsource (lib "eagle-import") (part "R_SMD0603"))
    )
    (comp (ref "R42")
      (value "220")
      (footprint "eagle-import:RESC1608X55")
      (libsource (lib "eagle-import") (part "R_SMD0603"))
    )
    (comp (ref "R53")
      (value "510")
      (footprint "eagle-import:RESC1005X40")
      (libsource (lib "eagle-import") (part "R_SMD0402"))
    )
    (comp (ref "R54")
      (value "10k")
      (footprint "eagle-import:RESC1005X40")
      (libsource (lib "eagle-import") (part "R_SMD0402"))
    )
    (comp (ref "T5")
      (value "SI2374DSSOT23-VSHAY")
      (footprint "eagle-import:SOT95P237X112-3")
      (libsource (lib "eagle-import") (part "SI2374DSSOT23-VSHAY"))
    )
    (comp (ref "T6")
      (value "SI2374DSSOT23-VSHAY")
      (footprint "eagle-import:SOT95P237X112-3")
      (libsource (lib "eagle-import") (part "SI2374DSSOT23-VSHAY"))
    )
    (comp (ref "T7")
      (value "SI2374DSSOT23-VSHAY")
      (footprint "eagle-import:SOT95P237X112-3")
      (libsource (lib "eagle-import") (part "SI2374DSSOT23-VSHAY"))
    )
    (comp (ref "C1")
      (value "0.1u")
      (footprint "eagle-import:CAPC1005X55")
      (libsource (lib "eagle-import") (part "C_SMD0402"))
    )
    (comp (ref "C2")
      (value "0.1u")
      (footprint "eagle-import:CAPC1005X55")
      (libsource (lib "eagle-import") (part "C_SMD0402"))
    )
    (comp (ref "C3")
      (value "0.1u")
      (footprint "eagle-import:CAPC1005X55")
      (libsource (lib "eagle-import") (part "C_SMD0402"))
    )
    (comp (ref "C4")
      (value "1n")
      (footprint "eagle-import:CAPC1005X55")
      (libsource (lib "eagle-import") (part "C_SMD0402"))
    )
    (comp (ref "C5")
      (value "1n")
      (footprint "eagle-import:CAPC1005X55")
      (libsource (lib "eagle-import") (part "C_SMD0402"))
    )
    (comp (ref "IC1")
      (value "AD8422BRMZ")
      (footprint "eagle-import:RM_8-L")
      (libsource (lib "eagle-import") (part "AD8422BRMZ"))
    )
    (comp (ref "IC2")
      (value "OPA2388DGK8_L")
      (footprint "eagle-import:DGK8-L")
      (libsource (lib "eagle-import") (part "OPA2388DGK8_L"))
    )
    (comp (ref "JP1")
      (value "PINHD-1X2")
      (footprint "eagle-import:1X02")
      (libsource (lib "eagle-import") (part "PINHD-1X2"))
    )
    (comp (ref "LED3")
      (value "598-8130-107FLED_0805")
      (footprint "eagle-import:LEDC2012X75")
      (libsource (lib "eagle-import") (part "598-8130-107FLED_0805"))
    )
    (comp (ref "LED4")
      (value "598-8130-107FLED_0805")
      (footprint "eagle-import:LEDC2012X75")
      (libsource (lib "eagle-import") (part "598-8130-107FLED_0805"))
    )
    (comp (ref "R1")
      (value "402")
      (footprint "eagle-import:RESC1608X55")
      (libsource (lib "eagle-import") (part "R_SMD0603"))
    )
    (comp (ref "R2")
      (value "2")
      (footprint "eagle-import:RESC1608X55")
      (libsource (lib "eagle-import") (part "R_SMD0603"))
    )
    (comp (ref "R3")
      (value "24")
      (footprint "eagle-import:RESC1005X40")
      (libsource (lib "eagle-import") (part "R_SMD0402"))
    )
    (comp (ref "R4")
      (value "2.4k")
      (footprint "eagle-import:RESC1005X40")
      (libsource (lib "eagle-import") (part "R_SMD0402"))
    )
    (comp (ref "R5")
      (value "3.6k")
      (footprint "eagle-import:RESC1005X40")
      (libsource (lib "eagle-import") (part "R_SMD0402"))
    )
    (comp (ref "R6")
      (value "10k")
      (footprint "eagle-import:RESC1005X40")
      (libsource (lib "eagle-import") (part "R_SMD0402"))
    )
    (comp (ref "R7")
      (value "10k")
      (footprint "eagle-import:RESC1005X40")
      (libsource (lib "eagle-import") (part "R_SMD0402"))
    )
    (comp (ref "R8")
      (value "1.2k")
      (footprint "eagle-import:RESC1005X40")
      (libsource (lib "eagle-import") (part "R_SMD0402"))
    )
    (comp (ref "R9")
      (value "91")
      (footprint "eagle-import:RESC1608X55")
      (libsource (lib "eagle-import") (part "R_SMD0603"))
    )
    (comp (ref "S1")
      (value "ADG849YKSZ-REELKS_6-L")
      (footprint "eagle-import:KS_6-L")
      (libsource (lib "eagle-import") (part "ADG849YKSZ-REELKS_6-L"))
    )
    (comp (ref "T1")
      (value "SI2374DSSOT23-VSHAY")
      (footprint "eagle-import:SOT95P237X112-3")
      (libsource (lib "eagle-import") (part "SI2374DSSOT23-VSHAY"))
    )
    (comp (ref "C42")
      (value "10n")
      (footprint "eagle-import:CAPC1005X55")
      (libsource (lib "eagle-import") (part "C_SMD0402"))
    )
    (comp (ref "C43")
      (value "4.7u")
      (footprint "eagle-import:CAPC2012X145")
      (libsource (lib "eagle-import") (part "C_SMD0805"))
    )
    (comp (ref "C44")
      (value "4.7u")
      (footprint "eagle-import:CAPC2012X145")
      (libsource (lib "eagle-import") (part "C_SMD0805"))
    )
    (comp (ref "C45")
      (value "0.1u")
      (footprint "eagle-import:CAPC1005X55")
      (libsource (lib "eagle-import") (part "C_SMD0402"))
    )
    (comp (ref "IC13")
      (value "BQ25504_RGT_16")
      (footprint "eagle-import:RGT16_1P7X1P7")
      (libsource (lib "eagle-import") (part "BQ25504_RGT_16"))
    )
    (comp (ref "L1")
      (value "22u")
      (footprint "eagle-import:L3225P")
      (libsource (lib "eagle-import") (part "L-EUL3225P"))
    )
    (comp (ref "ROK1")
      (value "5.62M")
      (footprint "eagle-import:RESC1608X55")
      (libsource (lib "eagle-import") (part "R_SMD0603"))
    )
    (comp (ref "ROK2")
      (value "5.62M")
      (footprint "eagle-import:RESC1608X55")
      (libsource (lib "eagle-import") (part "R_SMD0603"))
    )
    (comp (ref "ROK3")
      (value "1.87M")
      (footprint "eagle-import:RESC1608X55")
      (libsource (lib "eagle-import") (part "R_SMD0603"))
    )
    (comp (ref "ROV1")
      (value "5.62M")
      (footprint "eagle-import:RESC1608X55")
      (libsource (lib "eagle-import") (part "R_SMD0603"))
    )
    (comp (ref "ROV2")
      (value "5.62M")
      (footprint "eagle-import:RESC1608X55")
      (libsource (lib "eagle-import") (part "R_SMD0603"))
    )
    (comp (ref "RUV1")
      (value "5.62M")
      (footprint "eagle-import:RESC1608X55")
      (libsource (lib "eagle-import") (part "R_SMD0603"))
    )
    (comp (ref "RUV2")
      (value "3.6M")
      (footprint "eagle-import:RESC1608X55")
      (libsource (lib "eagle-import") (part "R_SMD0603"))
    )
    (comp (ref "S2")
      (value "ADG736LBRMZRM_10-L")
      (footprint "eagle-import:RM_10-L")
      (libsource (lib "eagle-import") (part "ADG736LBRMZRM_10-L"))
    )
  )
  (nets
    (net (code "1") (name "+3V3") (class "Default")
      (node (ref "C1") (pin "1") (pinfunction "1_1") (pintype "passive"))
      (node (ref "C21") (pin "1") (pinfunction "1_1") (pintype "passive"))
      (node (ref "C22") (pin "1") (pinfunction "1_1") (pintype "passive"))
      (node (ref "C26") (pin "1") (pinfunction "1_1") (pintype "passive"))
      (node (ref "C27") (pin "2") (pinfunction "2_2") (pintype "passive"))
      (node (ref "C38") (pin "1") (pinfunction "1_1") (pintype "passive"))
      (node (ref "C46") (pin "1") (pinfunction "1_1") (pintype "passive"))
      (node (ref "C51") (pin "1") (pinfunction "1_1") (pintype "passive"))
      (node (ref "IC11") (pin "8") (pinfunction "VCC_8") (pintype "bidirectional"))
      (node (ref "IC14") (pin "14") (pinfunction "VCC_14") (pintype "power_in"))
      (node (ref "IC16") (pin "11") (pinfunction "VCCB_11") (pintype "power_in"))
      (node (ref "IC2") (pin "8") (pinfunction "V+_8") (pintype "power_in"))
      (node (ref "IC5") (pin "34") (pinfunction "DVDD_34") (pintype "power_in"))
      (node (ref "IC7") (pin "3") (pinfunction "VDD_3") (pintype "power_in"))
      (node (ref "J1") (pin "1") (pinfunction "1_1") (pintype "passive"))
      (node (ref "P2") (pin "5") (pinfunction "5_5") (pintype "passive"))
      (node (ref "P3") (pin "1") (pinfunction "1_1") (pintype "passive"))
      (node (ref "P9") (pin "3") (pinfunction "3_3") (pintype "passive"))
      (node (ref "P9") (pin "4") (pinfunction "4_4") (pintype "passive"))
      (node (ref "R10") (pin "2") (pinfunction "2_2") (pintype "passive"))
      (node (ref "R22") (pin "2") (pinfunction "2_2") (pintype "passive"))
      (node (ref "R23") (pin "2") (pinfunction "2_2") (pintype "passive"))
      (node (ref "R41") (pin "2") (pinfunction "2_2") (pintype "passive"))
      (node (ref "R42") (pin "2") (pinfunction "2_2") (pintype "passive"))
      (node (ref "R47") (pin "2") (pinfunction "2_2") (pintype "passive"))
      (node (ref "R48") (pin "2") (pinfunction "2_2") (pintype "passive"))
      (node (ref "R49") (pin "2") (pinfunction "2_2") (pintype "passive"))
      (node (ref "R5") (pin "1") (pinfunction "1_1") (pintype "passive"))
      (node (ref "R50") (pin "2") (pinfunction "2_2") (pintype "passive"))
      (node (ref "R54") (pin "1") (pinfunction "1_1") (pintype "passive"))
    )
    (net (code "2") (name "+5V") (class "Default")
      (node (ref "C36") (pin "1") (pinfunction "1_1") (pintype "passive"))
      (node (ref "IC12") (pin "3") (pinfunction "VIN_3") (pintype "input"))
      (node (ref "P9") (pin "7") (pinfunction "7_7") (pintype "passive"))
      (node (ref "P9") (pin "8") (pinfunction "8_8") (pintype "passive"))
    )
    (net (code "3") (name "BUTTON_LED_OD") (class "Default")
      (node (ref "J1") (pin "2") (pinfunction "2_2") (pintype "passive"))
      (node (ref "R38") (pin "2") (pinfunction "2_2") (pintype "passive"))
    )
    (net (code "4") (name "CS_ADC") (class "Default")
      (node (ref "IC5") (pin "38") (pinfunction "CS_N_38") (pintype "input"))
      (node (ref "P9") (pin "25") (pinfunction "25_25") (pintype "passive"))
    )
    (net (code "5") (name "CS_DAC") (class "Default")
      (node (ref "IC10") (pin "6") (pinfunction "~{SYNC}_6") (pintype "input"))
      (node (ref "P9") (pin "31") (pinfunction "31_31") (pintype "passive"))
    )
    (net (code "6") (name "EN_HRVST") (class "Default")
      (node (ref "R32") (pin "2") (pinfunction "2_2") (pintype "passive"))
      (node (ref "T2") (pin "1") (pinfunction "G_1") (pintype "passive"))
    )
    (net (code "7") (name "EN_LVLCNV") (class "Default")
      (node (ref "IC16") (pin "12") (pinfunction "OE_12") (pintype "input"))
      (node (ref "R37") (pin "1") (pinfunction "1_1") (pintype "passive"))
    )
    (net (code "8") (name "EN_MPPT#") (class "Default")
      (node (ref "R34") (pin "2") (pinfunction "2_2") (pintype "passive"))
      (node (ref "S2") (pin "1") (pinfunction "IN1_1") (pintype "passive"))
      (node (ref "S2") (pin "5") (pinfunction "IN2_5") (pintype "passive"))
    )
    (net (code "9") (name "EN_V_ANLG") (class "Default")
      (node (ref "IC12") (pin "12") (pinfunction "EN_P_12") (pintype "input"))
      (node (ref "IC12") (pin "8") (pinfunction "EN_N_8") (pintype "input"))
      (node (ref "R40") (pin "1") (pinfunction "1_1") (pintype "passive"))
    )
    (net (code "10") (name "EN_V_FIX") (class "Default")
      (node (ref "P9") (pin "16") (pinfunction "16_16") (pintype "passive"))
      (node (ref "P9") (pin "29") (pinfunction "29_29") (pintype "passive"))
      (node (ref "S4") (pin "4") (pinfunction "SEL_4") (pintype "bidirectional"))
    )
    (net (code "11") (name "GND") (class "Default")
      (node (ref "C1") (pin "2") (pinfunction "2_2") (pintype "passive"))
      (node (ref "C11") (pin "2") (pinfunction "2_2") (pintype "passive"))
      (node (ref "C12") (pin "2") (pinfunction "2_2") (pintype "passive"))
      (node (ref "C13") (pin "2") (pinfunction "2_2") (pintype "passive"))
      (node (ref "C14") (pin "2") (pinfunction "2_2") (pintype "passive"))
      (node (ref "C15") (pin "2") (pinfunction "2_2") (pintype "passive"))
      (node (ref "C16") (pin "2") (pinfunction "2_2") (pintype "passive"))
      (node (ref "C17") (pin "2") (pinfunction "2_2") (pintype "passive"))
      (node (ref "C18") (pin "2") (pinfunction "2_2") (pintype "passive"))
      (node (ref "C19") (pin "2") (pinfunction "2_2") (pintype "passive"))
      (node (ref "C2") (pin "2") (pinfunction "2_2") (pintype "passive"))
      (node (ref "C20") (pin "2") (pinfunction "2_2") (pintype "passive"))
      (node (ref "C21") (pin "2") (pinfunction "2_2") (pintype "passive"))
      (node (ref "C22") (pin "2") (pinfunction "2_2") (pintype "passive"))
      (node (ref "C23") (pin "2") (pinfunction "2_2") (pintype "passive"))
      (node (ref "C26") (pin "2") (pinfunction "2_2") (pintype "passive"))
      (node (ref "C27") (pin "1") (pinfunction "1_1") (pintype "passive"))
      (node (ref "C28") (pin "2") (pinfunction "2_2") (pintype "passive"))
      (node (ref "C3") (pin "2") (pinfunction "2_2") (pintype "passive"))
      (node (ref "C30") (pin "2") (pinfunction "2_2") (pintype "passive"))
      (node (ref "C31") (pin "2") (pinfunction "2_2") (pintype "passive"))
      (node (ref "C32") (pin "2") (pinfunction "2_2") (pintype "passive"))
      (node (ref "C33") (pin "2") (pinfunction "2_2") (pintype "passive"))
      (node (ref "C34") (pin "2") (pinfunction "2_2") (pintype "passive"))
      (node (ref "C35") (pin "2") (pinfunction "2_2") (pintype "passive"))
      (node (ref "C36") (pin "2") (pinfunction "2_2") (pintype "passive"))
      (node (ref "C38") (pin "2") (pinfunction "2_2") (pintype "passive"))
      (node (ref "C39") (pin "2") (pinfunction "2_2") (pintype "passive"))
      (node (ref "C40") (pin "2") (pinfunction "2_2") (pintype "passive"))
      (node (ref "C41") (pin "2") (pinfunction "2_2") (pintype "passive"))
      (node (ref "C42") (pin "2") (pinfunction "2_2") (pintype "passive"))
      (node (ref "C43") (pin "2") (pinfunction "2_2") (pintype "passive"))
      (node (ref "C44") (pin "2") (pinfunction "2_2") (pintype "passive"))
      (node (ref "C45") (pin "2") (pinfunction "2_2") (pintype "passive"))
      (node (ref "C46") (pin "2") (pinfunction "2_2") (pintype "passive"))
      (node (ref "C48") (pin "2") (pinfunction "2_2") (pintype "passive"))
      (node (ref "C49") (pin "2") (pinfunction "2_2") (pintype "passive"))
      (node (ref "C50") (pin "2") (pinfunction "2_2") (pintype "passive"))
      (node (ref "C51") (pin "2") (pinfunction "2_2") (pintype "passive"))
      (node (ref "C52") (pin "2") (pinfunction "2_2") (pintype "passive"))
      (node (ref "C53") (pin "2") (pinfunction "2_2") (pintype "passive"))
      (node (ref "C6") (pin "2") (pinfunction "2_2") (pintype "passive"))
      (node (ref "C7") (pin "2") (pinfunction "2_2") (pintype "passive"))
      (node (ref "C8") (pin "2") (pinfunction "2_2") (pintype "passive"))
      (node (ref "D2") (pin "2") (pinfunction "A_2") (pintype "passive"))
      (node (ref "IC1") (pin "6") (pinfunction "REF_6") (pintype "input"))
      (node (ref "IC10") (pin "3") (pinfunction "GND_3") (pintype "power_in"))
      (node (ref "IC10") (pin "4") (pinfunction "~{LDAC}_4") (pintype "passive"))
      (node (ref "IC11") (pin "1") (pinfunction "A0_1") (pintype "bidirectional"))
      (node (ref "IC11") (pin "2") (pinfunction "A1_2") (pintype "bidirectional"))
      (node (ref "IC11") (pin "4") (pinfunction "VSS_4") (pintype "bidirectional"))
      (node (ref "IC12") (pin "1") (pinfunction "PGOOD_1") (pintype "output"))
      (node (ref "IC12") (pin "13") (pinfunction "EP_GND_13") (pintype "power_in"))
      (node (ref "IC12") (pin "4") (pinfunction "GND_4") (pintype "power_in"))
      (node (ref "IC13") (pin "1") (pinfunction "VSS_2_1") (pintype "power_in"))
      (node (ref "IC13") (pin "12") (pinfunction "AVSS_12") (pintype "power_in"))
      (node (ref "IC13") (pin "13") (pinfunction "VSS_13") (pintype "power_in"))
      (node (ref "IC13") (pin "17") (pinfunction "EPAD_17") (pintype "power_in"))
      (node (ref "IC13") (pin "5") (pinfunction "OT_PROG_5") (pintype "input"))
      (node (ref "IC14") (pin "1") (pinfunction "1OE_N_1") (pintype "input"))
      (node (ref "IC14") (pin "10") (pinfunction "3OE_N_10") (pintype "input"))
      (node (ref "IC14") (pin "13") (pinfunction "4OE_N_13") (pintype "input"))
      (node (ref "IC14") (pin "4") (pinfunction "2OE_N_4") (pintype "input"))
      (node (ref "IC14") (pin "7") (pinfunction "GND_7") (pintype "power_in"))
      (node (ref "IC15") (pin "2") (pinfunction "V-_2") (pintype "power_in"))
      (node (ref "IC16") (pin "6") (pinfunction "GND_6") (pintype "power_in"))
      (node (ref "IC2") (pin "4") (pinfunction "V-_4") (pintype "power_in"))
      (node (ref "IC3") (pin "6") (pinfunction "REF_6") (pintype "input"))
      (node (ref "IC4") (pin "4") (pinfunction "V-_4") (pintype "power_in"))
      (node (ref "IC5") (pin "17") (pinfunction "AIN_0GND_17") (pintype "power_in"))
      (node (ref "IC5") (pin "19") (pinfunction "AIN_1GND_19") (pintype "power_in"))
      (node (ref "IC5") (pin "20") (pinfunction "AIN2_GND_20") (pintype "power_in"))
      (node (ref "IC5") (pin "22") (pinfunction "AIN_3GND_22") (pintype "power_in"))
      (node (ref "IC5") (pin "28") (pinfunction "AGND_2_28") (pintype "power_in"))
      (node (ref "IC5") (pin "29") (pinfunction "AGND_3_29") (pintype "power_in"))
      (node (ref "IC5") (pin "3") (pinfunction "DAISY_3") (pintype "input"))
      (node (ref "IC5") (pin "31") (pinfunction "AGND_4_31") (pintype "power_in"))
      (node (ref "IC5") (pin "32") (pinfunction "AGND_5_32") (pintype "power_in"))
      (node (ref "IC5") (pin "33") (pinfunction "DGND_33") (pintype "power_in"))
      (node (ref "IC5") (pin "4") (pinfunction "REFSEL_N_4") (pintype "input"))
      (node (ref "IC5") (pin "6") (pinfunction "REFGND_6") (pintype "power_in"))
      (node (ref "IC5") (pin "8") (pinfunction "AGND_8") (pintype "power_in"))
      (node (ref "IC6") (pin "4") (pinfunction "V-_4") (pintype "power_in"))
      (node (ref "IC7") (pin "2") (pinfunction "GND_2") (pintype "power_in"))
      (node (ref "IC7") (pin "6") (pinfunction "A0_6") (pintype "input"))
      (node (ref "IC8") (pin "2") (pinfunction "GND_2") (pintype "passive"))
      (node (ref "J1") (pin "4") (pinfunction "4_4") (pintype "passive"))
      (node (ref "J1") (pin "5") (pinfunction "MNT_1_5") (pintype "passive"))
      (node (ref "J1") (pin "6") (pinfunction "MNT_2_6") (pintype "passive"))
      (node (ref "P1") (pin "1") (pinfunction "1_1") (pintype "passive"))
      (node (ref "P1") (pin "3") (pinfunction "3_3") (pintype "passive"))
      (node (ref "P2") (pin "16") (pinfunction "16_16") (pintype "passive"))
      (node (ref "P2") (pin "2") (pinfunction "2_2") (pintype "passive"))
      (node (ref "P2") (pin "7") (pinfunction "7_7") (pintype "passive"))
      (node (ref "P3") (pin "3") (pinfunction "3_3") (pintype "passive"))
      (node (ref "P3") (pin "4") (pinfunction "4_4") (pintype "passive"))
      (node (ref "P4") (pin "1") (pinfunction "1_1") (pintype "passive"))
      (node (ref "P4") (pin "2") (pinfunction "2_2") (pintype "passive"))
      (node (ref "P4") (pin "3") (pinfunction "3_3") (pintype "passive"))
      (node (ref "P4") (pin "4") (pinfunction "4_4") (pintype "passive"))
      (node (ref "P8") (pin "1") (pinfunction "1_1") (pintype "passive"))
      (node (ref "P8") (pin "2") (pinfunction "2_2") (pintype "passive"))
      (node (ref "P9") (pin "1") (pinfunction "1_1") (pintype "passive"))
      (node (ref "P9") (pin "2") (pinfunction "2_2") (pintype "passive"))
      (node (ref "P9") (pin "43") (pinfunction "43_43") (pintype "passive"))
      (node (ref "P9") (pin "44") (pinfunction "44_44") (pintype "passive"))
      (node (ref "P9") (pin "45") (pinfunction "45_45") (pintype "passive"))
      (node (ref "P9") (pin "46") (pinfunction "46_46") (pintype "passive"))
      (node (ref "R16") (pin "2") (pinfunction "2_2") (pintype "passive"))
      (node (ref "R26") (pin "2") (pinfunction "2_2") (pintype "passive"))
      (node (ref "R29") (pin "2") (pinfunction "2_2") (pintype "passive"))
      (node (ref "R44") (pin "1") (pinfunction "1_1") (pintype "passive"))
      (node (ref "R46") (pin "1") (pinfunction "1_1") (pintype "passive"))
      (node (ref "R6") (pin "2") (pinfunction "2_2") (pintype "passive"))
      (node (ref "ROK1") (pin "1") (pinfunction "1_1") (pintype "passive"))
      (node (ref "ROV1") (pin "1") (pinfunction "1_1") (pintype "passive"))
      (node (ref "RUV1") (pin "1") (pinfunction "1_1") (pintype "passive"))
      (node (ref "S1") (pin "3") (pinfunction "GND_3") (pintype "passive"))
      (node (ref "S2") (pin "3") (pinfunction "GND_3") (pintype "passive"))
      (node (ref "S4") (pin "3") (pinfunction "GND_3") (pintype "power_in"))
      (node (ref "T1") (pin "2") (pinfunction "S_2") (pintype "passive"))
      (node (ref "T2") (pin "2") (pinfunction "S_2") (pintype "passive"))
      (node (ref "T5") (pin "2") (pinfunction "S_2") (pintype "passive"))
      (node (ref "T6") (pin "2") (pinfunction "S_2") (pintype "passive"))
      (node (ref "T7") (pin "2") (pinfunction "S_2") (pintype "passive"))
    )
    (net (code "12") (name "GPIO0_BB") (class "Default")
      (node (ref "D5") (pin "2") (pinfunction "C_2") (pintype "passive"))
      (node (ref "P8") (pin "45") (pinfunction "45_45") (pintype "passive"))
    )
    (net (code "13") (name "GPIO0_TARGET") (class "Default")
      (node (ref "IC14") (pin "12") (pinfunction "4A_12") (pintype "input"))
      (node (ref "P2") (pin "10") (pinfunction "10_10") (pintype "passive"))
    )
    (net (code "14") (name "GPIO1_BB") (class "Default")
      (node (ref "D3") (pin "2") (pinfunction "C_2") (pintype "passive"))
      (node (ref "P8") (pin "46") (pinfunction "46_46") (pintype "passive"))
    )
    (net (code "15") (name "GPIO1_TARGET") (class "Default")
      (node (ref "IC14") (pin "5") (pinfunction "2A_5") (pintype "input"))
      (node (ref "P2") (pin "14") (pinfunction "14_14") (pintype "passive"))
    )
    (net (code "16") (name "GPIO2_BB") (class "Default")
      (node (ref "D6") (pin "2") (pinfunction "C_2") (pintype "passive"))
      (node (ref "P8") (pin "43") (pinfunction "43_43") (pintype "passive"))
    )
    (net (code "17") (name "GPIO2_TARGET") (class "Default")
      (node (ref "IC14") (pin "9") (pinfunction "3A_9") (pintype "input"))
      (node (ref "P2") (pin "8") (pinfunction "8_8") (pintype "passive"))
    )
    (net (code "18") (name "GPIO3_BB") (class "Default")
      (node (ref "D4") (pin "2") (pinfunction "C_2") (pintype "passive"))
      (node (ref "P8") (pin "44") (pinfunction "44_44") (pintype "passive"))
    )
    (net (code "19") (name "GPIO3_TARGET") (class "Default")
      (node (ref "IC14") (pin "2") (pinfunction "1A_2") (pintype "input"))
      (node (ref "P2") (pin "12") (pinfunction "12_12") (pintype "passive"))
    )
    (net (code "20") (name "I2C1_SCL") (class "Default")
      (node (ref "IC7") (pin "5") (pinfunction "SCL_5") (pintype "input"))
      (node (ref "P9") (pin "17") (pinfunction "17_17") (pintype "passive"))
      (node (ref "R22") (pin "1") (pinfunction "1_1") (pintype "passive"))
    )
    (net (code "21") (name "I2C1_SDA") (class "Default")
      (node (ref "IC7") (pin "4") (pinfunction "SDA_4") (pintype "input"))
      (node (ref "P9") (pin "18") (pinfunction "18_18") (pintype "passive"))
      (node (ref "R23") (pin "1") (pinfunction "1_1") (pintype "passive"))
    )
    (net (code "22") (name "I2C2_SCL") (class "Default")
      (node (ref "IC11") (pin "6") (pinfunction "SCL_6") (pintype "bidirectional"))
      (node (ref "P9") (pin "19") (pinfunction "19_19") (pintype "passive"))
      (node (ref "R47") (pin "1") (pinfunction "1_1") (pintype "passive"))
    )
    (net (code "23") (name "I2C2_SDA") (class "Default")
      (node (ref "IC11") (pin "5") (pinfunction "SDA_5") (pintype "bidirectional"))
      (node (ref "P9") (pin "20") (pinfunction "20_20") (pintype "passive"))
      (node (ref "R48") (pin "1") (pinfunction "1_1") (pintype "passive"))
    )
    (net (code "24") (name "LED_BUTTON") (class "Default")
      (node (ref "R53") (pin "1") (pinfunction "1_1") (pintype "passive"))
      (node (ref "T7") (pin "1") (pinfunction "G_1") (pintype "passive"))
    )
    (net (code "25") (name "LED_USR1") (class "Default")
      (node (ref "R35") (pin "1") (pinfunction "1_1") (pintype "passive"))
      (node (ref "T5") (pin "1") (pinfunction "G_1") (pintype "passive"))
    )
    (net (code "26") (name "LED_USR2") (class "Default")
      (node (ref "R36") (pin "1") (pinfunction "1_1") (pintype "passive"))
      (node (ref "T6") (pin "1") (pinfunction "G_1") (pintype "passive"))
    )
    (net (code "27") (name "MISO") (class "Default")
      (node (ref "IC5") (pin "36") (pinfunction "SDO_36") (pintype "output"))
      (node (ref "P9") (pin "27") (pinfunction "27_27") (pintype "passive"))
    )
    (net (code "28") (name "MOSI") (class "Default")
      (node (ref "IC10") (pin "8") (pinfunction "DIN_8") (pintype "input"))
      (node (ref "IC5") (pin "1") (pinfunction "SDI_1") (pintype "input"))
      (node (ref "P9") (pin "30") (pinfunction "30_30") (pintype "passive"))
    )
    (net (code "29") (name "Net-(D1-A)") (class "Default")
      (node (ref "D1") (pin "2") (pinfunction "A_2") (pintype "passive"))
      (node (ref "T4") (pin "3") (pinfunction "D_3") (pintype "passive"))
    )
    (net (code "30") (name "Net-(D3-A)") (class "Default")
      (node (ref "D3") (pin "1") (pinfunction "A_1") (pintype "passive"))
      (node (ref "IC14") (pin "6") (pinfunction "2Y_6") (pintype "tri_state"))
    )
    (net (code "31") (name "Net-(D4-A)") (class "Default")
      (node (ref "D4") (pin "1") (pinfunction "A_1") (pintype "passive"))
      (node (ref "IC14") (pin "3") (pinfunction "1Y_3") (pintype "tri_state"))
    )
    (net (code "32") (name "Net-(D5-A)") (class "Default")
      (node (ref "D5") (pin "1") (pinfunction "A_1") (pintype "passive"))
      (node (ref "IC14") (pin "11") (pinfunction "4Y_11") (pintype "tri_state"))
    )
    (net (code "33") (name "Net-(D6-A)") (class "Default")
      (node (ref "D6") (pin "1") (pinfunction "A_1") (pintype "passive"))
      (node (ref "IC14") (pin "8") (pinfunction "3Y_8") (pintype "tri_state"))
    )
    (net (code "34") (name "Net-(IC1-RG)") (class "Default")
      (node (ref "IC1") (pin "2") (pinfunction "RG_2") (pintype "passive"))
      (node (ref "R1") (pin "2") (pinfunction "2_2") (pintype "passive"))
    )
    (net (code "35") (name "Net-(IC1-RG_2)") (class "Default")
      (node (ref "IC1") (pin "3") (pinfunction "RG_2_3") (pintype "passive"))
      (node (ref "R1") (pin "1") (pinfunction "1_1") (pintype "passive"))
    )
    (net (code "36") (name "Net-(IC2A-IN+)") (class "Default")
      (node (ref "C5") (pin "1") (pinfunction "1_1") (pintype "passive"))
      (node (ref "IC2") (pin "3") (pinfunction "IN+_3") (pintype "input"))
      (node (ref "R4") (pin "2") (pinfunction "2_2") (pintype "passive"))
      (node (ref "R7") (pin "2") (pinfunction "2_2") (pintype "passive"))
    )
    (net (code "37") (name "Net-(IC2A-IN-)") (class "Default")
      (node (ref "IC2") (pin "2") (pinfunction "IN-_2") (pintype "input"))
      (node (ref "R5") (pin "2") (pinfunction "2_2") (pintype "passive"))
      (node (ref "R6") (pin "1") (pinfunction "1_1") (pintype "passive"))
    )
    (net (code "38") (name "Net-(IC2A-OUT)") (class "Default")
      (node (ref "C5") (pin "2") (pinfunction "2_2") (pintype "passive"))
      (node (ref "IC2") (pin "1") (pinfunction "OUT_1") (pintype "output"))
      (node (ref "R7") (pin "1") (pinfunction "1_1") (pintype "passive"))
      (node (ref "R8") (pin "2") (pinfunction "2_2") (pintype "passive"))
    )
    (net (code "39") (name "Net-(IC2B-IN-)") (class "Default")
      (node (ref "C4") (pin "1") (pinfunction "1_1") (pintype "passive"))
      (node (ref "IC2") (pin "6") (pinfunction "IN-_6") (pintype "input"))
      (node (ref "R3") (pin "1") (pinfunction "1_1") (pintype "passive"))
      (node (ref "R4") (pin "1") (pinfunction "1_1") (pintype "passive"))
    )
    (net (code "40") (name "Net-(IC2B-OUT)") (class "Default")
      (node (ref "C4") (pin "2") (pinfunction "2_2") (pintype "passive"))
      (node (ref "IC2") (pin "7") (pinfunction "OUT_7") (pintype "output"))
      (node (ref "R3") (pin "2") (pinfunction "2_2") (pintype "passive"))
    )
    (net (code "41") (name "Net-(IC3-RG)") (class "Default")
      (node (ref "IC3") (pin "2") (pinfunction "RG_2") (pintype "passive"))
      (node (ref "R12") (pin "1") (pinfunction "1_1") (pintype "passive"))
    )
    (net (code "42") (name "Net-(IC3-RG_2)") (class "Default")
      (node (ref "IC3") (pin "3") (pinfunction "RG_2_3") (pintype "passive"))
      (node (ref "R12") (pin "2") (pinfunction "2_2") (pintype "passive"))
    )
    (net (code "43") (name "Net-(IC4A-IN-)") (class "Default")
      (node (ref "C9") (pin "1") (pinfunction "1_1") (pintype "passive"))
      (node (ref "IC4") (pin "2") (pinfunction "IN-_2") (pintype "input"))
      (node (ref "R14") (pin "2") (pinfunction "2_2") (pintype "passive"))
    )
    (net (code "44") (name "Net-(IC4A-OUT)") (class "Default")
      (node (ref "C9") (pin "2") (pinfunction "2_2") (pintype "passive"))
      (node (ref "IC4") (pin "1") (pinfunction "OUT_1") (pintype "output"))
      (node (ref "R13") (pin "2") (pinfunction "2_2") (pintype "passive"))
    )
    (net (code "45") (name "Net-(IC4B-IN+)") (class "Default")
      (node (ref "IC4") (pin "5") (pinfunction "IN+_5") (pintype "input"))
      (node (ref "R15") (pin "2") (pinfunction "2_2") (pintype "passive"))
      (node (ref "T3") (pin "3") (pinfunction "D_3") (pintype "passive"))
    )
    (net (code "46") (name "Net-(IC4B-IN-)") (class "Default")
      (node (ref "C10") (pin "1") (pinfunction "1_1") (pintype "passive"))
      (node (ref "IC4") (pin "6") (pinfunction "IN-_6") (pintype "input"))
      (node (ref "R17") (pin "2") (pinfunction "2_2") (pintype "passive"))
    )
    (net (code "47") (name "Net-(IC4B-OUT)") (class "Default")
      (node (ref "C10") (pin "2") (pinfunction "2_2") (pintype "passive"))
      (node (ref "IC4") (pin "7") (pinfunction "OUT_7") (pintype "output"))
      (node (ref "R18") (pin "2") (pinfunction "2_2") (pintype "passive"))
    )
    (net (code "48") (name "Net-(IC5-AUX_GND)") (class "Default")
      (node (ref "IC5") (pin "10") (pinfunction "AUX_IN_10") (pintype "input"))
      (node (ref "IC5") (pin "11") (pinfunction "AUX_GND_11") (pintype "power_in"))
    )
    (net (code "49") (name "Net-(IC5-REFCAP)") (class "Default")
      (node (ref "C15") (pin "1") (pinfunction "1_1") (pintype "passive"))
      (node (ref "C17") (pin "1") (pinfunction "1_1") (pintype "passive"))
      (node (ref "IC5") (pin "7") (pinfunction "REFCAP_7") (pintype "passive"))
    )
    (net (code "50") (name "Net-(IC5-REFIO)") (class "Default")
      (node (ref "C13") (pin "1") (pinfunction "1_1") (pintype "passive"))
      (node (ref "IC5") (pin "5") (pinfunction "REFIO_5") (pintype "bidirectional"))
    )
    (net (code "51") (name "Net-(IC6A-OUT)") (class "Default")
      (node (ref "C25") (pin "2") (pinfunction "2_2") (pintype "passive"))
      (node (ref "IC6") (pin "1") (pinfunction "OUT_1") (pintype "output"))
      (node (ref "R21") (pin "1") (pinfunction "1_1") (pintype "passive"))
    )
    (net (code "52") (name "Net-(IC6B-OUT)") (class "Default")
      (node (ref "C24") (pin "2") (pinfunction "2_2") (pintype "passive"))
      (node (ref "IC6") (pin "7") (pinfunction "OUT_7") (pintype "output"))
      (node (ref "R20") (pin "1") (pinfunction "1_1") (pintype "passive"))
    )
    (net (code "53") (name "Net-(IC7-VOUT)") (class "Default")
      (node (ref "IC7") (pin "1") (pinfunction "VOUT_1") (pintype "output"))
      (node (ref "R24") (pin "1") (pinfunction "1_1") (pintype "passive"))
    )
    (net (code "54") (name "Net-(IC8-NR{slash}FB)") (class "Default")
      (node (ref "IC8") (pin "4") (pinfunction "NR/FB_4") (pintype "input"))
      (node (ref "R24") (pin "2") (pinfunction "2_2") (pintype "passive"))
      (node (ref "R25") (pin "2") (pinfunction "2_2") (pintype "passive"))
      (node (ref "R26") (pin "1") (pinfunction "1_1") (pintype "passive"))
    )
    (net (code "55") (name "Net-(IC8-OUT)") (class "Default")
      (node (ref "C52") (pin "1") (pinfunction "1_1") (pintype "passive"))
      (node (ref "IC8") (pin "5") (pinfunction "OUT_5") (pintype "output"))
      (node (ref "R25") (pin "1") (pinfunction "1_1") (pintype "passive"))
      (node (ref "S4") (pin "1") (pinfunction "D_1") (pintype "bidirectional"))
    )
    (net (code "56") (name "Net-(IC9-IN+)") (class "Default")
      (node (ref "IC9") (pin "3") (pinfunction "IN+_3") (pintype "input"))
      (node (ref "R28") (pin "1") (pinfunction "1_1") (pintype "passive"))
      (node (ref "R29") (pin "1") (pinfunction "1_1") (pintype "passive"))
    )
    (net (code "57") (name "Net-(IC9-IN-)") (class "Default")
      (node (ref "C29") (pin "1") (pinfunction "1_1") (pintype "passive"))
      (node (ref "IC9") (pin "4") (pinfunction "IN-_4") (pintype "input"))
      (node (ref "R27") (pin "1") (pinfunction "1_1") (pintype "passive"))
      (node (ref "R30") (pin "2") (pinfunction "2_2") (pintype "passive"))
    )
    (net (code "58") (name "Net-(IC10-~{CLR})") (class "Default")
      (node (ref "IC10") (pin "5") (pinfunction "~{CLR}_5") (pintype "input"))
      (node (ref "R31") (pin "2") (pinfunction "2_2") (pintype "passive"))
    )
    (net (code "59") (name "Net-(IC11-A2)") (class "Default")
      (node (ref "IC11") (pin "3") (pinfunction "A2_3") (pintype "bidirectional"))
      (node (ref "R49") (pin "1") (pinfunction "1_1") (pintype "passive"))
    )
    (net (code "60") (name "Net-(IC11-WP)") (class "Default")
      (node (ref "IC11") (pin "7") (pinfunction "WP_7") (pintype "bidirectional"))
      (node (ref "R50") (pin "1") (pinfunction "1_1") (pintype "passive"))
      (node (ref "WP") (pin "TP") (pinfunction "TP_TP") (pintype "input"))
    )
    (net (code "61") (name "Net-(IC12-C1_N)") (class "Default")
      (node (ref "C37") (pin "2") (pinfunction "2_2") (pintype "passive"))
      (node (ref "IC12") (pin "9") (pinfunction "C1_N_9") (pintype "input"))
    )
    (net (code "62") (name "Net-(IC12-C1_P)") (class "Default")
      (node (ref "C37") (pin "1") (pinfunction "1_1") (pintype "passive"))
      (node (ref "IC12") (pin "10") (pinfunction "C1_P_10") (pintype "input"))
    )
    (net (code "63") (name "Net-(IC12-CP)") (class "Default")
      (node (ref "C41") (pin "1") (pinfunction "1_1") (pintype "passive"))
      (node (ref "IC12") (pin "5") (pinfunction "CP_5") (pintype "output"))
    )
    (net (code "64") (name "Net-(IC12-FB_N)") (class "Default")
      (node (ref "IC12") (pin "7") (pinfunction "FB_N_7") (pintype "input"))
      (node (ref "R45") (pin "1") (pinfunction "1_1") (pintype "passive"))
      (node (ref "R46") (pin "2") (pinfunction "2_2") (pintype "passive"))
    )
    (net (code "65") (name "Net-(IC12-FB_P)") (class "Default")
      (node (ref "IC12") (pin "2") (pinfunction "FB_P_2") (pintype "input"))
      (node (ref "R43") (pin "1") (pinfunction "1_1") (pintype "passive"))
      (node (ref "R44") (pin "2") (pinfunction "2_2") (pintype "passive"))
    )
    (net (code "66") (name "Net-(IC13-LBST)") (class "Default")
      (node (ref "IC13") (pin "16") (pinfunction "LBST_16") (pintype "input"))
      (node (ref "L1") (pin "1") (pinfunction "1_1") (pintype "passive"))
    )
    (net (code "67") (name "Net-(IC15-IN-)") (class "Default")
      (node (ref "C47") (pin "2") (pinfunction "2_2") (pintype "passive"))
      (node (ref "IC15") (pin "4") (pinfunction "IN-_4") (pintype "input"))
      (node (ref "R52") (pin "2") (pinfunction "2_2") (pintype "passive"))
    )
    (net (code "68") (name "Net-(IC15-OUT)") (class "Default")
      (node (ref "C47") (pin "1") (pinfunction "1_1") (pintype "passive"))
      (node (ref "IC15") (pin "1") (pinfunction "OUT_1") (pintype "output"))
      (node (ref "R51") (pin "2") (pinfunction "2_2") (pintype "passive"))
      (node (ref "R52") (pin "1") (pinfunction "1_1") (pintype "passive"))
    )
    (net (code "69") (name "Net-(LED1-A)") (class "Default")
      (node (ref "LED1") (pin "2") (pinfunction "A_2") (pintype "passive"))
      (node (ref "R41") (pin "1") (pinfunction "1_1") (pintype "passive"))
    )
    (net (code "70") (name "Net-(LED1-C)") (class "Default")
      (node (ref "LED1") (pin "1") (pinfunction "C_1") (pintype "passive"))
      (node (ref "T5") (pin "3") (pinfunction "D_3") (pintype "passive"))
    )
    (net (code "71") (name "Net-(LED2-A)") (class "Default")
      (node (ref "LED2") (pin "2") (pinfunction "A_2") (pintype "passive"))
      (node (ref "R42") (pin "1") (pinfunction "1_1") (pintype "passive"))
    )
    (net (code "72") (name "Net-(LED2-C)") (class "Default")
      (node (ref "LED2") (pin "1") (pinfunction "C_1") (pintype "passive"))
      (node (ref "T6") (pin "3") (pinfunction "D_3") (pintype "passive"))
    )
    (net (code "73") (name "Net-(LED3-A)") (class "Default")
      (node (ref "LED3") (pin "2") (pinfunction "A_2") (pintype "passive"))
      (node (ref "LED4") (pin "2") (pinfunction "A_2") (pintype "passive"))
      (node (ref "R9") (pin "1") (pinfunction "1_1") (pintype "passive"))
    )
    (net (code "74") (name "Net-(LED3-C)") (class "Default")
      (node (ref "LED3") (pin "1") (pinfunction "C_1") (pintype "passive"))
      (node (ref "LED4") (pin "1") (pinfunction "C_1") (pintype "passive"))
      (node (ref "T1") (pin "3") (pinfunction "D_3") (pintype "passive"))
    )
    (net (code "75") (name "Net-(P8-Pad12)") (class "Default")
      (node (ref "P8") (pin "12") (pinfunction "12_12") (pintype "passive"))
      (node (ref "R35") (pin "2") (pinfunction "2_2") (pintype "passive"))
    )
    (net (code "76") (name "Net-(P8-Pad13)") (class "Default")
      (node (ref "P8") (pin "13") (pinfunction "13_13") (pintype "passive"))
      (node (ref "R32") (pin "1") (pinfunction "1_1") (pintype "passive"))
    )
    (net (code "77") (name "Net-(P8-Pad28)") (class "Default")
      (node (ref "P8") (pin "28") (pinfunction "28_28") (pintype "passive"))
      (node (ref "R39") (pin "2") (pinfunction "2_2") (pintype "passive"))
    )
    (net (code "78") (name "Net-(P8-Pad30)") (class "Default")
      (node (ref "P8") (pin "30") (pinfunction "30_30") (pintype "passive"))
      (node (ref "R36") (pin "2") (pinfunction "2_2") (pintype "passive"))
    )
    (net (code "79") (name "Net-(P8-Pad33)") (class "Default")
      (node (ref "P8") (pin "33") (pinfunction "33_33") (pintype "passive"))
      (node (ref "R53") (pin "2") (pinfunction "2_2") (pintype "passive"))
    )
    (net (code "80") (name "Net-(P8-Pad36)") (class "Default")
      (node (ref "P8") (pin "36") (pinfunction "36_36") (pintype "passive"))
      (node (ref "R37") (pin "2") (pinfunction "2_2") (pintype "passive"))
    )
    (net (code "81") (name "Net-(P9-Pad11)") (class "Default")
      (node (ref "P9") (pin "11") (pinfunction "11_11") (pintype "passive"))
      (node (ref "R34") (pin "1") (pinfunction "1_1") (pintype "passive"))
    )
    (net (code "82") (name "Net-(P9-Pad12)") (class "Default")
      (node (ref "P9") (pin "12") (pinfunction "12_12") (pintype "passive"))
      (node (ref "R40") (pin "2") (pinfunction "2_2") (pintype "passive"))
    )
    (net (code "83") (name "Net-(P9-Pad15)") (class "Default")
      (node (ref "P9") (pin "15") (pinfunction "15_15") (pintype "passive"))
      (node (ref "R33") (pin "1") (pinfunction "1_1") (pintype "passive"))
    )
    (net (code "84") (name "Net-(S3-A)") (class "Default")
      (node (ref "R10") (pin "1") (pinfunction "1_1") (pintype "passive"))
      (node (ref "S3") (pin "1") (pinfunction "A_1") (pintype "passive"))
    )
    (net (code "85") (name "Net-(S3-K)") (class "Default")
      (node (ref "S3") (pin "2") (pinfunction "K_2") (pintype "passive"))
      (node (ref "T2") (pin "3") (pinfunction "D_3") (pintype "passive"))
    )
    (net (code "86") (name "Net-(T1-G)") (class "Default")
      (node (ref "R8") (pin "1") (pinfunction "1_1") (pintype "passive"))
      (node (ref "T1") (pin "1") (pinfunction "G_1") (pintype "passive"))
    )
    (net (code "87") (name "Net-(T3-G)") (class "Default")
      (node (ref "R13") (pin "1") (pinfunction "1_1") (pintype "passive"))
      (node (ref "T3") (pin "1") (pinfunction "G_1") (pintype "passive"))
    )
    (net (code "88") (name "Net-(T3-S)") (class "Default")
      (node (ref "R14") (pin "1") (pinfunction "1_1") (pintype "passive"))
      (node (ref "R16") (pin "1") (pinfunction "1_1") (pintype "passive"))
      (node (ref "T3") (pin "2") (pinfunction "S_2") (pintype "passive"))
      (node (ref "TP1") (pin "TP") (pinfunction "TP_TP") (pintype "input"))
    )
    (net (code "89") (name "Net-(T4-G)") (class "Default")
      (node (ref "R18") (pin "1") (pinfunction "1_1") (pintype "passive"))
      (node (ref "T4") (pin "1") (pinfunction "G_1") (pintype "passive"))
    )
    (net (code "90") (name "Net-(T4-S)") (class "Default")
      (node (ref "R17") (pin "1") (pinfunction "1_1") (pintype "passive"))
      (node (ref "R19") (pin "2") (pinfunction "2_2") (pintype "passive"))
      (node (ref "T4") (pin "2") (pinfunction "S_2") (pintype "passive"))
      (node (ref "TP2") (pin "TP") (pinfunction "TP_TP") (pintype "input"))
    )
    (net (code "91") (name "Net-(T7-D)") (class "Default")
      (node (ref "R38") (pin "1") (pinfunction "1_1") (pintype "passive"))
      (node (ref "T7") (pin "3") (pinfunction "D_3") (pintype "passive"))
    )
    (net (code "92") (name "RST{slash}PDN_ADC") (class "Default")
      (node (ref "IC5") (pin "2") (pinfunction "RST_PD_N_2") (pintype "input"))
      (node (ref "R39") (pin "1") (pinfunction "1_1") (pintype "passive"))
    )
    (net (code "93") (name "SCLK") (class "Default")
      (node (ref "IC10") (pin "7") (pinfunction "SCLK_7") (pintype "input"))
      (node (ref "IC5") (pin "37") (pinfunction "SCLK_37") (pintype "input"))
      (node (ref "P9") (pin "28") (pinfunction "28_28") (pintype "passive"))
    )
    (net (code "94") (name "SENSE_BUTTON") (class "Default")
      (node (ref "J1") (pin "3") (pinfunction "3_3") (pintype "passive"))
      (node (ref "P8") (pin "34") (pinfunction "34_34") (pintype "passive"))
      (node (ref "R54") (pin "2") (pinfunction "2_2") (pintype "passive"))
    )
    (net (code "95") (name "SLCT_LOAD") (class "Default")
      (node (ref "R33") (pin "2") (pinfunction "2_2") (pintype "passive"))
      (node (ref "S1") (pin "1") (pinfunction "IN_1") (pintype "passive"))
    )
    (net (code "96") (name "SWDCLK_BB") (class "Default")
      (node (ref "IC16") (pin "9") (pinfunction "B2_9") (pintype "bidirectional"))
      (node (ref "P9") (pin "42") (pinfunction "42_42") (pintype "passive"))
    )
    (net (code "97") (name "SWDCLK_TARGET") (class "Default")
      (node (ref "IC16") (pin "3") (pinfunction "A2_3") (pintype "bidirectional"))
      (node (ref "P2") (pin "13") (pinfunction "13_13") (pintype "passive"))
    )
    (net (code "98") (name "SWDIO_BB") (class "Default")
      (node (ref "IC16") (pin "10") (pinfunction "B1_10") (pintype "bidirectional"))
      (node (ref "P9") (pin "41") (pinfunction "41_41") (pintype "passive"))
    )
    (net (code "99") (name "SWDIO_TARGET") (class "Default")
      (node (ref "IC16") (pin "2") (pinfunction "A1_2") (pintype "bidirectional"))
      (node (ref "P2") (pin "15") (pinfunction "15_15") (pintype "passive"))
    )
    (net (code "100") (name "UART_RX_BB") (class "Default")
      (node (ref "IC16") (pin "7") (pinfunction "B4_7") (pintype "bidirectional"))
      (node (ref "P9") (pin "26") (pinfunction "26_26") (pintype "passive"))
    )
    (net (code "101") (name "UART_RX_TARGET") (class "Default")
      (node (ref "IC16") (pin "4") (pinfunction "A3_4") (pintype "bidirectional"))
      (node (ref "P2") (pin "11") (pinfunction "11_11") (pintype "passive"))
    )
    (net (code "102") (name "UART_TX_BB") (class "Default")
      (node (ref "IC16") (pin "8") (pinfunction "B3_8") (pintype "bidirectional"))
      (node (ref "P9") (pin "24") (pinfunction "24_24") (pintype "passive"))
    )
    (net (code "103") (name "UART_TX_TARGET") (class "Default")
      (node (ref "IC16") (pin "5") (pinfunction "A4_5") (pintype "bidirectional"))
      (node (ref "P2") (pin "9") (pinfunction "9_9") (pintype "passive"))
    )
    (net (code "104") (name "VDD") (class "Default")
      (node (ref "C11") (pin "1") (pinfunction "1_1") (pintype "passive"))
      (node (ref "C12") (pin "1") (pinfunction "1_1") (pintype "passive"))
      (node (ref "C14") (pin "1") (pinfunction "1_1") (pintype "passive"))
      (node (ref "C16") (pin "1") (pinfunction "1_1") (pintype "passive"))
      (node (ref "C18") (pin "1") (pinfunction "1_1") (pintype "passive"))
      (node (ref "C19") (pin "1") (pinfunction "1_1") (pintype "passive"))
      (node (ref "C2") (pin "1") (pinfunction "1_1") (pintype "passive"))
      (node (ref "C20") (pin "1") (pinfunction "1_1") (pintype "passive"))
      (node (ref "C23") (pin "1") (pinfunction "1_1") (pintype "passive"))
      (node (ref "C28") (pin "1") (pinfunction "1_1") (pintype "passive"))
      (node (ref "C31") (pin "1") (pinfunction "1_1") (pintype "passive"))
      (node (ref "C32") (pin "1") (pinfunction "1_1") (pintype "passive"))
      (node (ref "C33") (pin "1") (pinfunction "1_1") (pintype "passive"))
      (node (ref "C34") (pin "1") (pinfunction "1_1") (pintype "passive"))
      (node (ref "C40") (pin "1") (pinfunction "1_1") (pintype "passive"))
      (node (ref "C48") (pin "1") (pinfunction "1_1") (pintype "passive"))
      (node (ref "C53") (pin "1") (pinfunction "1_1") (pintype "passive"))
      (node (ref "C6") (pin "1") (pinfunction "1_1") (pintype "passive"))
      (node (ref "C8") (pin "1") (pinfunction "1_1") (pintype "passive"))
      (node (ref "IC1") (pin "8") (pinfunction "V+_8") (pintype "power_in"))
      (node (ref "IC10") (pin "9") (pinfunction "AVDD_9") (pintype "power_in"))
      (node (ref "IC12") (pin "11") (pinfunction "OUT_P_11") (pintype "output"))
      (node (ref "IC15") (pin "5") (pinfunction "V+_5") (pintype "power_in"))
      (node (ref "IC3") (pin "8") (pinfunction "V+_8") (pintype "power_in"))
      (node (ref "IC4") (pin "8") (pinfunction "V+_8") (pintype "power_in"))
      (node (ref "IC5") (pin "30") (pinfunction "AVDD_2_30") (pintype "power_in"))
      (node (ref "IC5") (pin "9") (pinfunction "AVDD_9") (pintype "power_in"))
      (node (ref "IC6") (pin "8") (pinfunction "V+_8") (pintype "power_in"))
      (node (ref "IC8") (pin "1") (pinfunction "IN_1") (pintype "power_in"))
      (node (ref "IC8") (pin "3") (pinfunction "EN_3") (pintype "input"))
      (node (ref "IC9") (pin "5") (pinfunction "V+_5") (pintype "power_in"))
      (node (ref "R15") (pin "1") (pinfunction "1_1") (pintype "passive"))
      (node (ref "R19") (pin "1") (pinfunction "1_1") (pintype "passive"))
      (node (ref "R31") (pin "1") (pinfunction "1_1") (pintype "passive"))
      (node (ref "R43") (pin "2") (pinfunction "2_2") (pintype "passive"))
      (node (ref "S1") (pin "2") (pinfunction "VDD_2") (pintype "power_in"))
      (node (ref "S2") (pin "8") (pinfunction "VDD_8") (pintype "passive"))
      (node (ref "S4") (pin "5") (pinfunction "VDD_5") (pintype "power_in"))
      (node (ref "TP5") (pin "TP") (pinfunction "TP_TP") (pintype "input"))
    )
    (net (code "105") (name "VDD_TARGET") (class "Default")
      (node (ref "C50") (pin "1") (pinfunction "1_1") (pintype "passive"))
      (node (ref "IC16") (pin "1") (pinfunction "VCCA_1") (pintype "power_in"))
      (node (ref "R51") (pin "1") (pinfunction "1_1") (pintype "passive"))
    )
    (net (code "106") (name "VOC_SAMP") (class "Default")
      (node (ref "IC13") (pin "3") (pinfunction "VOC_SAMP_3") (pintype "input"))
      (node (ref "S2") (pin "10") (pinfunction "D1_10") (pintype "passive"))
    )
    (net (code "107") (name "VOC_VD") (class "Default")
      (node (ref "P1") (pin "4") (pinfunction "4_4") (pintype "passive"))
      (node (ref "S2") (pin "9") (pinfunction "S1B_9") (pintype "passive"))
    )
    (net (code "108") (name "VREF_SAMP") (class "Default")
      (node (ref "IC13") (pin "4") (pinfunction "VREF_SAMP_4") (pintype "input"))
      (node (ref "S2") (pin "6") (pinfunction "D2_6") (pintype "passive"))
    )
    (net (code "109") (name "VSS") (class "Default")
      (node (ref "C3") (pin "1") (pinfunction "1_1") (pintype "passive"))
      (node (ref "C30") (pin "1") (pinfunction "1_1") (pintype "passive"))
      (node (ref "C39") (pin "1") (pinfunction "1_1") (pintype "passive"))
      (node (ref "C7") (pin "1") (pinfunction "1_1") (pintype "passive"))
      (node (ref "IC1") (pin "5") (pinfunction "V-_5") (pintype "power_in"))
      (node (ref "IC12") (pin "6") (pinfunction "OUT_N_6") (pintype "output"))
      (node (ref "IC3") (pin "5") (pinfunction "V-_5") (pintype "power_in"))
      (node (ref "IC9") (pin "2") (pinfunction "V-_2") (pintype "power_in"))
      (node (ref "R45") (pin "2") (pinfunction "2_2") (pintype "passive"))
      (node (ref "TP6") (pin "TP") (pinfunction "TP_TP") (pintype "input"))
    )
    (net (code "110") (name "V_AIN") (class "Default")
      (node (ref "IC3") (pin "7") (pinfunction "OUT_7") (pintype "output"))
      (node (ref "IC5") (pin "21") (pinfunction "AIN_2P_21") (pintype "input"))
      (node (ref "TP4") (pin "TP") (pinfunction "TP_TP") (pintype "input"))
    )
    (net (code "111") (name "V_AOUT") (class "Default")
      (node (ref "IC1") (pin "7") (pinfunction "OUT_7") (pintype "output"))
      (node (ref "IC5") (pin "23") (pinfunction "AIN_3P_23") (pintype "input"))
      (node (ref "TP3") (pin "TP") (pinfunction "TP_TP") (pintype "input"))
    )
    (net (code "112") (name "V_BAT") (class "Default")
      (node (ref "IC13") (pin "14") (pinfunction "VBAT_14") (pintype "bidirectional"))
      (node (ref "P3") (pin "2") (pinfunction "2_2") (pintype "passive"))
    )
    (net (code "113") (name "V_BATOK") (class "Default")
      (node (ref "IC13") (pin "11") (pinfunction "VBAT_OK_11") (pintype "output"))
      (node (ref "P2") (pin "3") (pinfunction "3_3") (pintype "passive"))
    )
    (net (code "114") (name "V_BQ") (class "Default")
      (node (ref "C43") (pin "1") (pinfunction "1_1") (pintype "passive"))
      (node (ref "IC13") (pin "2") (pinfunction "VIN_DC_2") (pintype "input"))
      (node (ref "JP2") (pin "1") (pinfunction "1_1") (pintype "passive"))
      (node (ref "L1") (pin "2") (pinfunction "2_2") (pintype "passive"))
    )
    (net (code "115") (name "V_CREF") (class "Default")
      (node (ref "C42") (pin "1") (pinfunction "1_1") (pintype "passive"))
      (node (ref "S2") (pin "7") (pinfunction "S2B_7") (pintype "passive"))
    )
    (net (code "116") (name "V_EMU_I") (class "Default")
      (node (ref "IC10") (pin "1") (pinfunction "VOUTA_1") (pintype "output"))
      (node (ref "R28") (pin "2") (pinfunction "2_2") (pintype "passive"))
    )
    (net (code "117") (name "V_EMU_I_BIASED") (class "Default")
      (node (ref "C29") (pin "2") (pinfunction "2_2") (pintype "passive"))
      (node (ref "IC4") (pin "3") (pinfunction "IN+_3") (pintype "input"))
      (node (ref "IC9") (pin "1") (pinfunction "OUT_1") (pintype "output"))
      (node (ref "R30") (pin "1") (pinfunction "1_1") (pintype "passive"))
    )
    (net (code "118") (name "V_EMU_V") (class "Default")
      (node (ref "IC10") (pin "2") (pinfunction "VOUTB_2") (pintype "output"))
      (node (ref "S2") (pin "4") (pinfunction "S2A_4") (pintype "passive"))
    )
    (net (code "119") (name "V_H") (class "Default")
      (node (ref "D2") (pin "1") (pinfunction "C_1") (pintype "passive"))
      (node (ref "P1") (pin "2") (pinfunction "2_2") (pintype "passive"))
      (node (ref "S3") (pin "4") (pinfunction "D2_4") (pintype "passive"))
    )
    (net (code "120") (name "V_IN_SHT+") (class "Default")
      (node (ref "D1") (pin "1") (pinfunction "C_1") (pintype "passive"))
      (node (ref "IC3") (pin "4") (pinfunction "IN+_4") (pintype "input"))
      (node (ref "P2") (pin "4") (pinfunction "4_4") (pintype "passive"))
      (node (ref "R11") (pin "2") (pinfunction "2_2") (pintype "passive"))
      (node (ref "S3") (pin "6") (pinfunction "D1_6") (pintype "passive"))
    )
    (net (code "121") (name "V_IN_SHT-") (class "Default")
      (node (ref "IC3") (pin "1") (pinfunction "IN-_1") (pintype "input"))
      (node (ref "IC6") (pin "5") (pinfunction "IN+_5") (pintype "input"))
      (node (ref "JP2") (pin "2") (pinfunction "2_2") (pintype "passive"))
      (node (ref "P2") (pin "6") (pinfunction "6_6") (pintype "passive"))
      (node (ref "R11") (pin "1") (pinfunction "1_1") (pintype "passive"))
    )
    (net (code "122") (name "V_LD_SHT+") (class "Default")
      (node (ref "IC1") (pin "4") (pinfunction "IN+_4") (pintype "input"))
      (node (ref "JP1") (pin "2") (pinfunction "2_2") (pintype "passive"))
      (node (ref "R2") (pin "2") (pinfunction "2_2") (pintype "passive"))
      (node (ref "S4") (pin "2") (pinfunction "S_2") (pintype "bidirectional"))
    )
    (net (code "123") (name "V_LOAD") (class "Default")
      (node (ref "IC1") (pin "1") (pinfunction "IN-_1") (pintype "input"))
      (node (ref "IC6") (pin "3") (pinfunction "IN+_3") (pintype "input"))
      (node (ref "R2") (pin "1") (pinfunction "1_1") (pintype "passive"))
      (node (ref "S1") (pin "5") (pinfunction "D_5") (pintype "passive"))
    )
    (net (code "124") (name "V_OK_HYST") (class "Default")
      (node (ref "IC13") (pin "9") (pinfunction "OK_HYST_9") (pintype "input"))
      (node (ref "ROK2") (pin "2") (pinfunction "2_2") (pintype "passive"))
      (node (ref "ROK3") (pin "1") (pinfunction "1_1") (pintype "passive"))
    )
    (net (code "125") (name "V_OK_PROG") (class "Default")
      (node (ref "IC13") (pin "10") (pinfunction "OK_PROG_10") (pintype "input"))
      (node (ref "ROK1") (pin "2") (pinfunction "2_2") (pintype "passive"))
      (node (ref "ROK2") (pin "1") (pinfunction "1_1") (pintype "passive"))
    )
    (net (code "126") (name "V_REF_2V5") (class "Default")
      (node (ref "C35") (pin "1") (pinfunction "1_1") (pintype "passive"))
      (node (ref "IC10") (pin "10") (pinfunction "VREFIN/VREFOUT_10") (pintype "bidirectional"))
      (node (ref "R27") (pin "2") (pinfunction "2_2") (pintype "passive"))
    )
    (net (code "127") (name "V_STR") (class "Default")
      (node (ref "C44") (pin "1") (pinfunction "1_1") (pintype "passive"))
      (node (ref "C45") (pin "1") (pinfunction "1_1") (pintype "passive"))
      (node (ref "IC13") (pin "15") (pinfunction "VSTOR_15") (pintype "output"))
      (node (ref "JP1") (pin "1") (pinfunction "1_1") (pintype "passive"))
      (node (ref "S2") (pin "2") (pinfunction "S1A_2") (pintype "passive"))
    )
    (net (code "128") (name "V_SUP_DUMMY") (class "Default")
      (node (ref "IC2") (pin "5") (pinfunction "IN+_5") (pintype "input"))
      (node (ref "R9") (pin "2") (pinfunction "2_2") (pintype "passive"))
      (node (ref "S1") (pin "4") (pinfunction "S1_4") (pintype "passive"))
    )
    (net (code "129") (name "V_SUP_TARGET") (class "Default")
      (node (ref "C49") (pin "1") (pinfunction "1_1") (pintype "passive"))
      (node (ref "IC15") (pin "3") (pinfunction "IN+_3") (pintype "input"))
      (node (ref "P2") (pin "1") (pinfunction "1_1") (pintype "passive"))
      (node (ref "S1") (pin "6") (pinfunction "S2_6") (pintype "passive"))
    )
    (net (code "130") (name "V_VBAT_OV") (class "Default")
      (node (ref "IC13") (pin "6") (pinfunction "VBAT_OV_6") (pintype "input"))
      (node (ref "ROV1") (pin "2") (pinfunction "2_2") (pintype "passive"))
      (node (ref "ROV2") (pin "1") (pinfunction "1_1") (pintype "passive"))
    )
    (net (code "131") (name "V_VBAT_UV") (class "Default")
      (node (ref "IC13") (pin "8") (pinfunction "VBAT_UV_8") (pintype "input"))
      (node (ref "RUV1") (pin "2") (pinfunction "2_2") (pintype "passive"))
      (node (ref "RUV2") (pin "1") (pinfunction "1_1") (pintype "passive"))
    )
    (net (code "132") (name "V_VIN") (class "Default")
      (node (ref "C24") (pin "1") (pinfunction "1_1") (pintype "passive"))
      (node (ref "IC5") (pin "16") (pinfunction "AIN_0P_16") (pintype "input"))
      (node (ref "IC6") (pin "6") (pinfunction "IN-_6") (pintype "input"))
      (node (ref "R20") (pin "2") (pinfunction "2_2") (pintype "passive"))
    )
    (net (code "133") (name "V_VOUT") (class "Default")
      (node (ref "C25") (pin "1") (pinfunction "1_1") (pintype "passive"))
      (node (ref "IC5") (pin "18") (pinfunction "AIN_1P_18") (pintype "input"))
      (node (ref "IC6") (pin "2") (pinfunction "IN-_2") (pintype "input"))
      (node (ref "R21") (pin "2") (pinfunction "2_2") (pintype "passive"))
    )
    (net (code "134") (name "V_VRDIV") (class "Default")
      (node (ref "IC13") (pin "7") (pinfunction "VRDIV_7") (pintype "output"))
      (node (ref "ROK3") (pin "2") (pinfunction "2_2") (pintype "passive"))
      (node (ref "ROV2") (pin "2") (pinfunction "2_2") (pintype "passive"))
      (node (ref "RUV2") (pin "2") (pinfunction "2_2") (pintype "passive"))
    )
    (net (code "135") (name "unconnected-(IC5-ALARM-Pad35)") (class "Default")
      (node (ref "IC5") (pin "35") (pinfunction "ALARM_35") (pintype "output"))
    )
    (net (code "136") (name "unconnected-(IC5-NC-Pad12)") (class "Default")
      (node (ref "IC5") (pin "12") (pinfunction "NC_12") (pintype "passive"))
    )
    (net (code "137") (name "unconnected-(IC5-NC_2-Pad13)") (class "Default")
      (node (ref "IC5") (pin "13") (pinfunction "NC_2_13") (pintype "passive"))
    )
    (net (code "138") (name "unconnected-(IC5-NC_3-Pad14)") (class "Default")
      (node (ref "IC5") (pin "14") (pinfunction "NC_3_14") (pintype "passive"))
    )
    (net (code "139") (name "unconnected-(IC5-NC_4-Pad15)") (class "Default")
      (node (ref "IC5") (pin "15") (pinfunction "NC_4_15") (pintype "passive"))
    )
    (net (code "140") (name "unconnected-(IC5-NC_5-Pad24)") (class "Default")
      (node (ref "IC5") (pin "24") (pinfunction "NC_5_24") (pintype "passive"))
    )
    (net (code "141") (name "unconnected-(IC5-NC_6-Pad25)") (class "Default")
      (node (ref "IC5") (pin "25") (pinfunction "NC_6_25") (pintype "passive"))
    )
    (net (code "142") (name "unconnected-(IC5-NC_7-Pad26)") (class "Default")
      (node (ref "IC5") (pin "26") (pinfunction "NC_7_26") (pintype "passive"))
    )
    (net (code "143") (name "unconnected-(IC5-NC_8-Pad27)") (class "Default")
      (node (ref "IC5") (pin "27") (pinfunction "NC_8_27") (pintype "passive"))
    )
    (net (code "144") (name "unconnected-(P8-Pad3)") (class "Default")
      (node (ref "P8") (pin "3") (pinfunction "3_3") (pintype "passive"))
    )
    (net (code "145") (name "unconnected-(P8-Pad4)") (class "Default")
      (node (ref "P8") (pin "4") (pinfunction "4_4") (pintype "passive"))
    )
    (net (code "146") (name "unconnected-(P8-Pad5)") (class "Default")
      (node (ref "P8") (pin "5") (pinfunction "5_5") (pintype "passive"))
    )
    (net (code "147") (name "unconnected-(P8-Pad6)") (class "Default")
      (node (ref "P8") (pin "6") (pinfunction "6_6") (pintype "passive"))
    )
    (net (code "148") (name "unconnected-(P8-Pad7)") (class "Default")
      (node (ref "P8") (pin "7") (pinfunction "7_7") (pintype "passive"))
    )
    (net (code "149") (name "unconnected-(P8-Pad8)") (class "Default")
      (node (ref "P8") (pin "8") (pinfunction "8_8") (pintype "passive"))
    )
    (net (code "150") (name "unconnected-(P8-Pad9)") (class "Default")
      (node (ref "P8") (pin "9") (pinfunction "9_9") (pintype "passive"))
    )
    (net (code "151") (name "unconnected-(P8-Pad10)") (class "Default")
      (node (ref "P8") (pin "10") (pinfunction "10_10") (pintype "passive"))
    )
    (net (code "152") (name "unconnected-(P8-Pad11)") (class "Default")
      (node (ref "P8") (pin "11") (pinfunction "11_11") (pintype "passive"))
    )
    (net (code "153") (name "unconnected-(P8-Pad14)") (class "Default")
      (node (ref "P8") (pin "14") (pinfunction "14_14") (pintype "passive"))
    )
    (net (code "154") (name "unconnected-(P8-Pad15)") (class "Default")
      (node (ref "P8") (pin "15") (pinfunction "15_15") (pintype "passive"))
    )
    (net (code "155") (name "unconnected-(P8-Pad16)") (class "Default")
      (node (ref "P8") (pin "16") (pinfunction "16_16") (pintype "passive"))
    )
    (net (code "156") (name "unconnected-(P8-Pad17)") (class "Default")
      (node (ref "P8") (pin "17") (pinfunction "17_17") (pintype "passive"))
    )
    (net (code "157") (name "unconnected-(P8-Pad18)") (class "Default")
      (node (ref "P8") (pin "18") (pinfunction "18_18") (pintype "passive"))
    )
    (net (code "158") (name "unconnected-(P8-Pad19)") (class "Default")
      (node (ref "P8") (pin "19") (pinfunction "19_19") (pintype "passive"))
    )
    (net (code "159") (name "unconnected-(P8-Pad20)") (class "Default")
      (node (ref "P8") (pin "20") (pinfunction "20_20") (pintype "passive"))
    )
    (net (code "160") (name "unconnected-(P8-Pad21)") (class "Default")
      (node (ref "P8") (pin "21") (pinfunction "21_21") (pintype "passive"))
    )
    (net (code "161") (name "unconnected-(P8-Pad22)") (class "Default")
      (node (ref "P8") (pin "22") (pinfunction "22_22") (pintype "passive"))
    )
    (net (code "162") (name "unconnected-(P8-Pad23)") (class "Default")
      (node (ref "P8") (pin "23") (pinfunction "23_23") (pintype "passive"))
    )
    (net (code "163") (name "unconnected-(P8-Pad24)") (class "Default")
      (node (ref "P8") (pin "24") (pinfunction "24_24") (pintype "passive"))
    )
    (net (code "164") (name "unconnected-(P8-Pad25)") (class "Default")
      (node (ref "P8") (pin "25") (pinfunction "25_25") (pintype "passive"))
    )
    (net (code "165") (name "unconnected-(P8-Pad26)") (class "Default")
      (node (ref "P8") (pin "26") (pinfunction "26_26") (pintype "passive"))
    )
    (net (code "166") (name "unconnected-(P8-Pad27)") (class "Default")
      (node (ref "P8") (pin "27") (pinfunction "27_27") (pintype "passive"))
    )
    (net (code "167") (name "unconnected-(P8-Pad29)") (class "Default")
      (node (ref "P8") (pin "29") (pinfunction "29_29") (pintype "passive"))
    )
    (net (code "168") (name "unconnected-(P8-Pad31)") (class "Default")
      (node (ref "P8") (pin "31") (pinfunction "31_31") (pintype "passive"))
    )
    (net (code "169") (name "unconnected-(P8-Pad32)") (class "Default")
      (node (ref "P8") (pin "32") (pinfunction "32_32") (pintype "passive"))
    )
    (net (code "170") (name "unconnected-(P8-Pad35)") (class "Default")
      (node (ref "P8") (pin "35") (pinfunction "35_35") (pintype "passive"))
    )
    (net (code "171") (name "unconnected-(P8-Pad37)") (class "Default")
      (node (ref "P8") (pin "37") (pinfunction "37_37") (pintype "passive"))
    )
    (net (code "172") (name "unconnected-(P8-Pad38)") (class "Default")
      (node (ref "P8") (pin "38") (pinfunction "38_38") (pintype "passive"))
    )
    (net (code "173") (name "unconnected-(P8-Pad39)") (class "Default")
      (node (ref "P8") (pin "39") (pinfunction "39_39") (pintype "passive"))
    )
    (net (code "174") (name "unconnected-(P8-Pad40)") (class "Default")
      (node (ref "P8") (pin "40") (pinfunction "40_40") (pintype "passive"))
    )
    (net (code "175") (name "unconnected-(P8-Pad41)") (class "Default")
      (node (ref "P8") (pin "41") (pinfunction "41_41") (pintype "passive"))
    )
    (net (code "176") (name "unconnected-(P8-Pad42)") (class "Default")
      (node (ref "P8") (pin "42") (pinfunction "42_42") (pintype "passive"))
    )
    (net (code "177") (name "unconnected-(P9-Pad5)") (class "Default")
      (node (ref "P9") (pin "5") (pinfunction "5_5") (pintype "passive"))
    )
    (net (code "178") (name "unconnected-(P9-Pad6)") (class "Default")
      (node (ref "P9") (pin "6") (pinfunction "6_6") (pintype "passive"))
    )
    (net (code "179") (name "unconnected-(P9-Pad9)") (class "Default")
      (node (ref "P9") (pin "9") (pinfunction "9_9") (pintype "passive"))
    )
    (net (code "180") (name "unconnected-(P9-Pad10)") (class "Default")
      (node (ref "P9") (pin "10") (pinfunction "10_10") (pintype "passive"))
    )
    (net (code "181") (name "unconnected-(P9-Pad13)") (class "Default")
      (node (ref "P9") (pin "13") (pinfunction "13_13") (pintype "passive"))
    )
    (net (code "182") (name "unconnected-(P9-Pad14)") (class "Default")
      (node (ref "P9") (pin "14") (pinfunction "14_14") (pintype "passive"))
    )
    (net (code "183") (name "unconnected-(P9-Pad21)") (class "Default")
      (node (ref "P9") (pin "21") (pinfunction "21_21") (pintype "passive"))
    )
    (net (code "184") (name "unconnected-(P9-Pad22)") (class "Default")
      (node (ref "P9") (pin "22") (pinfunction "22_22") (pintype "passive"))
    )
    (net (code "185") (name "unconnected-(P9-Pad23)") (class "Default")
      (node (ref "P9") (pin "23") (pinfunction "23_23") (pintype "passive"))
    )
    (net (code "186") (name "unconnected-(P9-Pad32)") (class "Default")
      (node (ref "P9") (pin "32") (pinfunction "32_32") (pintype "passive"))
    )
    (net (code "187") (name "unconnected-(P9-Pad33)") (class "Default")
      (node (ref "P9") (pin "33") (pinfunction "33_33") (pintype "passive"))
    )
    (net (code "188") (name "unconnected-(P9-Pad34)") (class "Default")
      (node (ref "P9") (pin "34") (pinfunction "34_34") (pintype "passive"))
    )
    (net (code "189") (name "unconnected-(P9-Pad35)") (class "Default")
      (node (ref "P9") (pin "35") (pinfunction "35_35") (pintype "passive"))
    )
    (net (code "190") (name "unconnected-(P9-Pad36)") (class "Default")
      (node (ref "P9") (pin "36") (pinfunction "36_36") (pintype "passive"))
    )
    (net (code "191") (name "unconnected-(P9-Pad37)") (class "Default")
      (node (ref "P9") (pin "37") (pinfunction "37_37") (pintype "passive"))
    )
    (net (code "192") (name "unconnected-(P9-Pad38)") (class "Default")
      (node (ref "P9") (pin "38") (pinfunction "38_38") (pintype "passive"))
    )
    (net (code "193") (name "unconnected-(P9-Pad39)") (class "Default")
      (node (ref "P9") (pin "39") (pinfunction "39_39") (pintype "passive"))
    )
    (net (code "194") (name "unconnected-(P9-Pad40)") (class "Default")
      (node (ref "P9") (pin "40") (pinfunction "40_40") (pintype "passive"))
    )
    (net (code "195") (name "unconnected-(S3-S-Pad5)") (class "Default")
      (node (ref "S3") (pin "5") (pinfunction "S_5") (pintype "passive"))
    )
  )
)
